# FPGA.net
KiCad netlist of a schematic drawn in Altium Designer
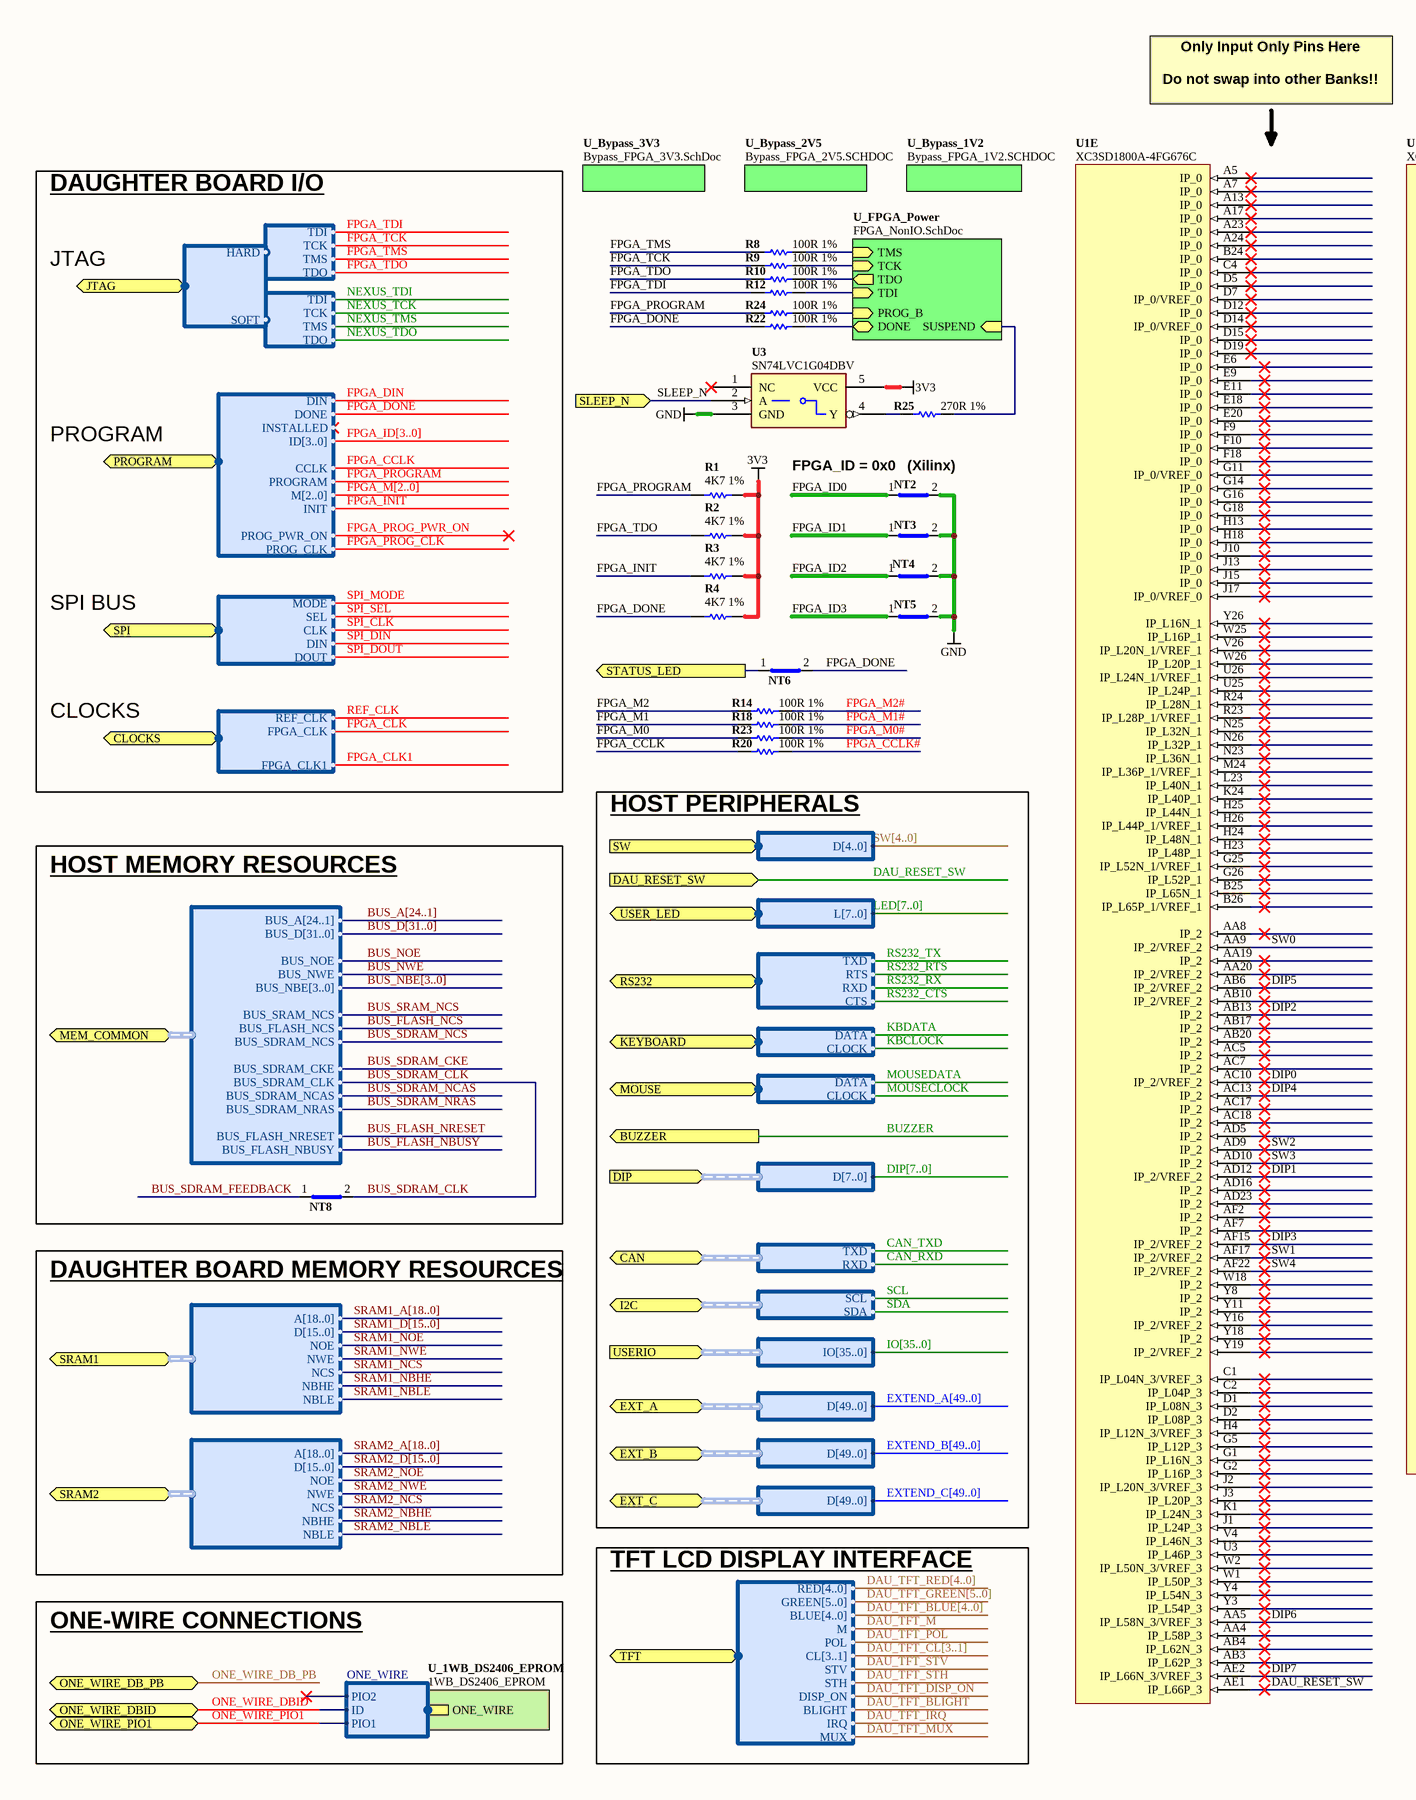
[diagram p0: FPGA.SCHDOC, left]
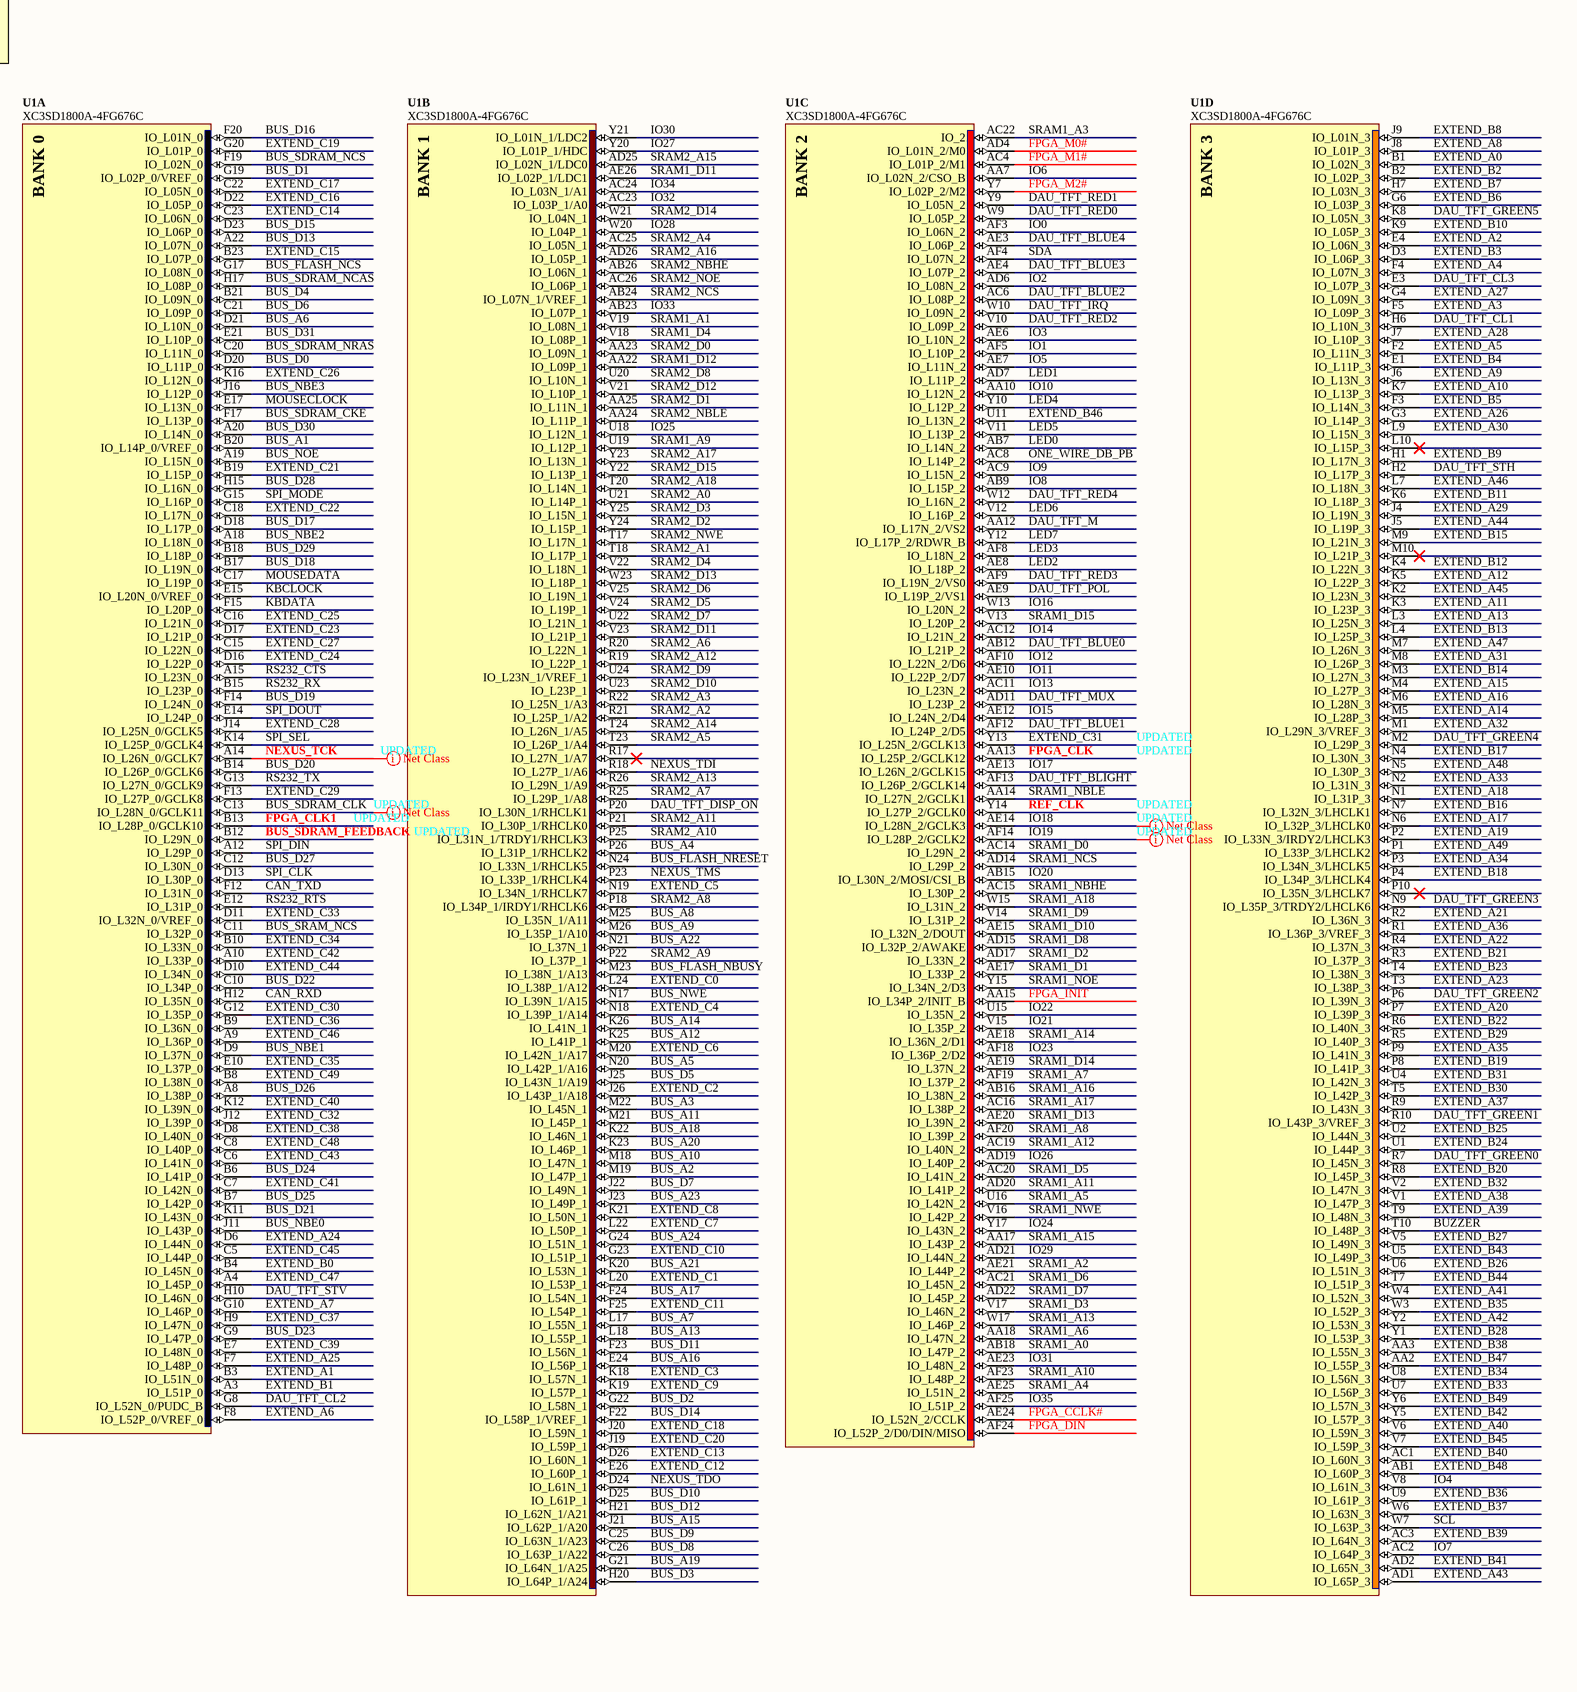
[diagram p1: FPGA.SCHDOC, right]

(export (version "E")
  (design (tool "Eeschema 10.0.6"))
  (components
    (comp (ref "NT2")
      (value "Net Tie SMT2")
      (footprint "NETTIE-SMT2-8X8")
      (description "Net-Tie, Surface Mount, 2 x 0.4mm x 0.2mm SMT Pads - For 0.2mm Track")
      (libsource (lib "AltiumDesignLibrary") (part "NETTIE-SMT2"))
    )
    (comp (ref "NT3")
      (value "Net Tie SMT2")
      (footprint "NETTIE-SMT2-8X8")
      (description "Net-Tie, Surface Mount, 2 x 0.4mm x 0.2mm SMT Pads - For 0.2mm Track")
      (libsource (lib "AltiumDesignLibrary") (part "NETTIE-SMT2"))
    )
    (comp (ref "NT4")
      (value "Net Tie SMT2")
      (footprint "NETTIE-SMT2-8X8")
      (description "Net-Tie, Surface Mount, 2 x 0.4mm x 0.2mm SMT Pads - For 0.2mm Track")
      (libsource (lib "AltiumDesignLibrary") (part "NETTIE-SMT2"))
    )
    (comp (ref "NT5")
      (value "Net Tie SMT2")
      (footprint "NETTIE-SMT2-8X8")
      (description "Net-Tie, Surface Mount, 2 x 0.4mm x 0.2mm SMT Pads - For 0.2mm Track")
      (libsource (lib "AltiumDesignLibrary") (part "NETTIE-SMT2"))
    )
    (comp (ref "NT6")
      (value "Net Tie SMT2")
      (footprint "NETTIE-SMT2-8X8")
      (description "Net-Tie, Surface Mount, 2 x 0.4mm x 0.2mm SMT Pads - For 0.2mm Track")
      (libsource (lib "AltiumDesignLibrary") (part "NETTIE-SMT2"))
    )
    (comp (ref "NT8")
      (value "Net Tie SMT2")
      (footprint "NETTIE-SMT2-8X8")
      (description "Net-Tie, Surface Mount, 2 x 0.4mm x 0.2mm SMT Pads - For 0.2mm Track")
      (libsource (lib "AltiumDesignLibrary") (part "NETTIE-SMT2"))
    )
    (comp (ref "R1")
      (value "4K7 1%")
      (footprint "RESC1005-STAR")
      (description "Resistor, 4K7 1% 0402 (1005)")
      (fields (field (name "TOLERANCE") "1 %"))
      (libsource (lib "AltiumDesignLibrary") (part "RES"))
    )
    (comp (ref "R2")
      (value "4K7 1%")
      (footprint "RESC1005-STAR")
      (description "Resistor, 4K7 1% 0402 (1005)")
      (fields (field (name "TOLERANCE") "1 %"))
      (libsource (lib "AltiumDesignLibrary") (part "RES"))
    )
    (comp (ref "R3")
      (value "4K7 1%")
      (footprint "RESC1005-STAR")
      (description "Resistor, 4K7 1% 0402 (1005)")
      (fields (field (name "TOLERANCE") "1 %"))
      (libsource (lib "AltiumDesignLibrary") (part "RES"))
    )
    (comp (ref "R4")
      (value "4K7 1%")
      (footprint "RESC1005-STAR")
      (description "Resistor, 4K7 1% 0402 (1005)")
      (fields (field (name "TOLERANCE") "1 %"))
      (libsource (lib "AltiumDesignLibrary") (part "RES"))
    )
    (comp (ref "R8")
      (value "100R 1%")
      (footprint "RESC1005-STAR")
      (description "Resistor, 100R 1% 0402 (1005)")
      (fields (field (name "TOLERANCE") "1 %"))
      (libsource (lib "AltiumDesignLibrary") (part "RES"))
    )
    (comp (ref "R9")
      (value "100R 1%")
      (footprint "RESC1005-STAR")
      (description "Resistor, 100R 1% 0402 (1005)")
      (fields (field (name "TOLERANCE") "1 %"))
      (libsource (lib "AltiumDesignLibrary") (part "RES"))
    )
    (comp (ref "R10")
      (value "100R 1%")
      (footprint "RESC1005-STAR")
      (description "Resistor, 100R 1% 0402 (1005)")
      (fields (field (name "TOLERANCE") "1 %"))
      (libsource (lib "AltiumDesignLibrary") (part "RES"))
    )
    (comp (ref "R12")
      (value "100R 1%")
      (footprint "RESC1005-STAR")
      (description "Resistor, 100R 1% 0402 (1005)")
      (fields (field (name "TOLERANCE") "1 %"))
      (libsource (lib "AltiumDesignLibrary") (part "RES"))
    )
    (comp (ref "R14")
      (value "100R 1%")
      (footprint "RESC1005-STAR")
      (description "Resistor, 100R 1% 0402 (1005)")
      (fields (field (name "TOLERANCE") "1 %"))
      (libsource (lib "AltiumDesignLibrary") (part "RES"))
    )
    (comp (ref "R18")
      (value "100R 1%")
      (footprint "RESC1005-STAR")
      (description "Resistor, 100R 1% 0402 (1005)")
      (fields (field (name "TOLERANCE") "1 %"))
      (libsource (lib "AltiumDesignLibrary") (part "RES"))
    )
    (comp (ref "R20")
      (value "100R 1%")
      (footprint "RESC1005-STAR")
      (description "Resistor, 100R 1% 0402 (1005)")
      (fields (field (name "TOLERANCE") "1 %"))
      (libsource (lib "AltiumDesignLibrary") (part "RES"))
    )
    (comp (ref "R22")
      (value "100R 1%")
      (footprint "RESC1005-STAR")
      (description "Resistor, 100R 1% 0402 (1005)")
      (fields (field (name "TOLERANCE") "1 %"))
      (libsource (lib "AltiumDesignLibrary") (part "RES"))
    )
    (comp (ref "R23")
      (value "100R 1%")
      (footprint "RESC1005-STAR")
      (description "Resistor, 100R 1% 0402 (1005)")
      (fields (field (name "TOLERANCE") "1 %"))
      (libsource (lib "AltiumDesignLibrary") (part "RES"))
    )
    (comp (ref "R24")
      (value "100R 1%")
      (footprint "RESC1005-STAR")
      (description "Resistor, 100R 1% 0402 (1005)")
      (fields (field (name "TOLERANCE") "1 %"))
      (libsource (lib "AltiumDesignLibrary") (part "RES"))
    )
    (comp (ref "R25")
      (value "270R 1%")
      (footprint "RESC1005-STAR")
      (description "Resistor, 270R 1% 0402 (1005)")
      (fields (field (name "TOLERANCE") "1 %"))
      (libsource (lib "AltiumDesignLibrary") (part "RES"))
    )
    (comp (ref "U1")
      (value "XC3SD1800A-4FG676C")
      (footprint "BGA100P26X26-676")
      (description "FPGA, Xilinx Spartan 3A-DSP-1800 FG676")
      (libsource (lib "AltiumDesignLibrary") (part "XC3SD1800A-4FG676C"))
    )
    (comp (ref "U3")
      (value "SN74LVC1G04DBV")
      (footprint "SOT95P280-5")
      (description "SN74LVC1G04DBV, Single Inverter Gate, 1.65-V to 5.5-V")
      (libsource (lib "AltiumDesignLibrary") (part "SN74LVC1G04DBV"))
    )
  )
  (nets
    (net (code "17") (name "/BUS_A1") (class "Default")
      (node (ref "U1") (pin "B20") (pinfunction "IO_L14P_0/VREF_0_B20") (pintype "bidirectional"))
    )
    (net (code "18") (name "/BUS_A2") (class "Default")
      (node (ref "U1") (pin "M19") (pinfunction "IO_L47P_1_M19") (pintype "bidirectional"))
    )
    (net (code "19") (name "/BUS_A3") (class "Default")
      (node (ref "U1") (pin "M22") (pinfunction "IO_L45N_1_M22") (pintype "bidirectional"))
    )
    (net (code "20") (name "/BUS_A4") (class "Default")
      (node (ref "U1") (pin "P26") (pinfunction "IO_L31P_1/RHCLK2_P26") (pintype "bidirectional"))
    )
    (net (code "21") (name "/BUS_A5") (class "Default")
      (node (ref "U1") (pin "N20") (pinfunction "IO_L42P_1/A16_N20") (pintype "bidirectional"))
    )
    (net (code "22") (name "/BUS_A6") (class "Default")
      (node (ref "U1") (pin "D21") (pinfunction "IO_L10N_0_D21") (pintype "bidirectional"))
    )
    (net (code "23") (name "/BUS_A7") (class "Default")
      (node (ref "U1") (pin "L17") (pinfunction "IO_L55N_1_L17") (pintype "bidirectional"))
    )
    (net (code "24") (name "/BUS_A8") (class "Default")
      (node (ref "U1") (pin "M25") (pinfunction "IO_L35N_1/A11_M25") (pintype "bidirectional"))
    )
    (net (code "25") (name "/BUS_A9") (class "Default")
      (node (ref "U1") (pin "M26") (pinfunction "IO_L35P_1/A10_M26") (pintype "bidirectional"))
    )
    (net (code "26") (name "/BUS_A10") (class "Default")
      (node (ref "U1") (pin "M18") (pinfunction "IO_L47N_1_M18") (pintype "bidirectional"))
    )
    (net (code "27") (name "/BUS_A11") (class "Default")
      (node (ref "U1") (pin "M21") (pinfunction "IO_L45P_1_M21") (pintype "bidirectional"))
    )
    (net (code "28") (name "/BUS_A12") (class "Default")
      (node (ref "U1") (pin "K25") (pinfunction "IO_L41P_1_K25") (pintype "bidirectional"))
    )
    (net (code "29") (name "/BUS_A13") (class "Default")
      (node (ref "U1") (pin "L18") (pinfunction "IO_L55P_1_L18") (pintype "bidirectional"))
    )
    (net (code "30") (name "/BUS_A14") (class "Default")
      (node (ref "U1") (pin "K26") (pinfunction "IO_L41N_1_K26") (pintype "bidirectional"))
    )
    (net (code "31") (name "/BUS_A15") (class "Default")
      (node (ref "U1") (pin "J21") (pinfunction "IO_L62P_1/A20_J21") (pintype "bidirectional"))
    )
    (net (code "32") (name "/BUS_A16") (class "Default")
      (node (ref "U1") (pin "E24") (pinfunction "IO_L56P_1_E24") (pintype "bidirectional"))
    )
    (net (code "33") (name "/BUS_A17") (class "Default")
      (node (ref "U1") (pin "F24") (pinfunction "IO_L54N_1_F24") (pintype "bidirectional"))
    )
    (net (code "34") (name "/BUS_A18") (class "Default")
      (node (ref "U1") (pin "K22") (pinfunction "IO_L46N_1_K22") (pintype "bidirectional"))
    )
    (net (code "35") (name "/BUS_A19") (class "Default")
      (node (ref "U1") (pin "G21") (pinfunction "IO_L64N_1/A25_G21") (pintype "bidirectional"))
    )
    (net (code "36") (name "/BUS_A20") (class "Default")
      (node (ref "U1") (pin "K23") (pinfunction "IO_L46P_1_K23") (pintype "bidirectional"))
    )
    (net (code "37") (name "/BUS_A21") (class "Default")
      (node (ref "U1") (pin "K20") (pinfunction "IO_L53N_1_K20") (pintype "bidirectional"))
    )
    (net (code "38") (name "/BUS_A22") (class "Default")
      (node (ref "U1") (pin "N21") (pinfunction "IO_L37N_1_N21") (pintype "bidirectional"))
    )
    (net (code "39") (name "/BUS_A23") (class "Default")
      (node (ref "U1") (pin "J23") (pinfunction "IO_L49P_1_J23") (pintype "bidirectional"))
    )
    (net (code "40") (name "/BUS_A24") (class "Default")
      (node (ref "U1") (pin "G24") (pinfunction "IO_L51N_1_G24") (pintype "bidirectional"))
    )
    (net (code "41") (name "/BUS_D0") (class "Default")
      (node (ref "U1") (pin "D20") (pinfunction "IO_L11P_0_D20") (pintype "bidirectional"))
    )
    (net (code "42") (name "/BUS_D1") (class "Default")
      (node (ref "U1") (pin "G19") (pinfunction "IO_L02P_0/VREF_0_G19") (pintype "bidirectional"))
    )
    (net (code "43") (name "/BUS_D2") (class "Default")
      (node (ref "U1") (pin "G22") (pinfunction "IO_L58N_1_G22") (pintype "bidirectional"))
    )
    (net (code "44") (name "/BUS_D3") (class "Default")
      (node (ref "U1") (pin "H20") (pinfunction "IO_L64P_1/A24_H20") (pintype "bidirectional"))
    )
    (net (code "45") (name "/BUS_D4") (class "Default")
      (node (ref "U1") (pin "B21") (pinfunction "IO_L09N_0_B21") (pintype "bidirectional"))
    )
    (net (code "46") (name "/BUS_D5") (class "Default")
      (node (ref "U1") (pin "J25") (pinfunction "IO_L43N_1/A19_J25") (pintype "bidirectional"))
    )
    (net (code "47") (name "/BUS_D6") (class "Default")
      (node (ref "U1") (pin "C21") (pinfunction "IO_L09P_0_C21") (pintype "bidirectional"))
    )
    (net (code "48") (name "/BUS_D7") (class "Default")
      (node (ref "U1") (pin "J22") (pinfunction "IO_L49N_1_J22") (pintype "bidirectional"))
    )
    (net (code "49") (name "/BUS_D8") (class "Default")
      (node (ref "U1") (pin "C26") (pinfunction "IO_L63P_1/A22_C26") (pintype "bidirectional"))
    )
    (net (code "50") (name "/BUS_D9") (class "Default")
      (node (ref "U1") (pin "C25") (pinfunction "IO_L63N_1/A23_C25") (pintype "bidirectional"))
    )
    (net (code "51") (name "/BUS_D10") (class "Default")
      (node (ref "U1") (pin "D25") (pinfunction "IO_L61P_1_D25") (pintype "bidirectional"))
    )
    (net (code "52") (name "/BUS_D11") (class "Default")
      (node (ref "U1") (pin "F23") (pinfunction "IO_L56N_1_F23") (pintype "bidirectional"))
    )
    (net (code "53") (name "/BUS_D12") (class "Default")
      (node (ref "U1") (pin "H21") (pinfunction "IO_L62N_1/A21_H21") (pintype "bidirectional"))
    )
    (net (code "54") (name "/BUS_D13") (class "Default")
      (node (ref "U1") (pin "A22") (pinfunction "IO_L07N_0_A22") (pintype "bidirectional"))
    )
    (net (code "55") (name "/BUS_D14") (class "Default")
      (node (ref "U1") (pin "F22") (pinfunction "IO_L58P_1/VREF_1_F22") (pintype "bidirectional"))
    )
    (net (code "56") (name "/BUS_D15") (class "Default")
      (node (ref "U1") (pin "D23") (pinfunction "IO_L06P_0_D23") (pintype "bidirectional"))
    )
    (net (code "57") (name "/BUS_D16") (class "Default")
      (node (ref "U1") (pin "F20") (pinfunction "IO_L01N_0_F20") (pintype "bidirectional"))
    )
    (net (code "58") (name "/BUS_D17") (class "Default")
      (node (ref "U1") (pin "D18") (pinfunction "IO_L17P_0_D18") (pintype "bidirectional"))
    )
    (net (code "59") (name "/BUS_D18") (class "Default")
      (node (ref "U1") (pin "B17") (pinfunction "IO_L19N_0_B17") (pintype "bidirectional"))
    )
    (net (code "60") (name "/BUS_D19") (class "Default")
      (node (ref "U1") (pin "F14") (pinfunction "IO_L24N_0_F14") (pintype "bidirectional"))
    )
    (net (code "61") (name "/BUS_D20") (class "Default")
      (node (ref "U1") (pin "B14") (pinfunction "IO_L26P_0/GCLK6_B14") (pintype "bidirectional"))
    )
    (net (code "62") (name "/BUS_D21") (class "Default")
      (node (ref "U1") (pin "K11") (pinfunction "IO_L43N_0_K11") (pintype "bidirectional"))
    )
    (net (code "63") (name "/BUS_D22") (class "Default")
      (node (ref "U1") (pin "C10") (pinfunction "IO_L34P_0_C10") (pintype "bidirectional"))
    )
    (net (code "64") (name "/BUS_D23") (class "Default")
      (node (ref "U1") (pin "G9") (pinfunction "IO_L47P_0_G9") (pintype "bidirectional"))
    )
    (net (code "65") (name "/BUS_D24") (class "Default")
      (node (ref "U1") (pin "B6") (pinfunction "IO_L41P_0_B6") (pintype "bidirectional"))
    )
    (net (code "66") (name "/BUS_D25") (class "Default")
      (node (ref "U1") (pin "B7") (pinfunction "IO_L42P_0_B7") (pintype "bidirectional"))
    )
    (net (code "67") (name "/BUS_D26") (class "Default")
      (node (ref "U1") (pin "A8") (pinfunction "IO_L38P_0_A8") (pintype "bidirectional"))
    )
    (net (code "68") (name "/BUS_D27") (class "Default")
      (node (ref "U1") (pin "C12") (pinfunction "IO_L30N_0_C12") (pintype "bidirectional"))
    )
    (net (code "69") (name "/BUS_D28") (class "Default")
      (node (ref "U1") (pin "H15") (pinfunction "IO_L16N_0_H15") (pintype "bidirectional"))
    )
    (net (code "70") (name "/BUS_D29") (class "Default")
      (node (ref "U1") (pin "B18") (pinfunction "IO_L18P_0_B18") (pintype "bidirectional"))
    )
    (net (code "71") (name "/BUS_D30") (class "Default")
      (node (ref "U1") (pin "A20") (pinfunction "IO_L14N_0_A20") (pintype "bidirectional"))
    )
    (net (code "72") (name "/BUS_D31") (class "Default")
      (node (ref "U1") (pin "E21") (pinfunction "IO_L10P_0_E21") (pintype "bidirectional"))
    )
    (net (code "74") (name "/BUS_FLASH_NBUSY") (class "Default")
      (node (ref "U1") (pin "M23") (pinfunction "IO_L38N_1/A13_M23") (pintype "bidirectional"))
    )
    (net (code "75") (name "/BUS_FLASH_NCS") (class "Default")
      (node (ref "U1") (pin "G17") (pinfunction "IO_L08N_0_G17") (pintype "bidirectional"))
    )
    (net (code "76") (name "/BUS_FLASH_NRESET") (class "Default")
      (node (ref "U1") (pin "N24") (pinfunction "IO_L33N_1/RHCLK5_N24") (pintype "bidirectional"))
    )
    (net (code "77") (name "/BUS_NBE0") (class "Default")
      (node (ref "U1") (pin "J11") (pinfunction "IO_L43P_0_J11") (pintype "bidirectional"))
    )
    (net (code "78") (name "/BUS_NBE1") (class "Default")
      (node (ref "U1") (pin "D9") (pinfunction "IO_L37N_0_D9") (pintype "bidirectional"))
    )
    (net (code "79") (name "/BUS_NBE2") (class "Default")
      (node (ref "U1") (pin "A18") (pinfunction "IO_L18N_0_A18") (pintype "bidirectional"))
    )
    (net (code "80") (name "/BUS_NBE3") (class "Default")
      (node (ref "U1") (pin "J16") (pinfunction "IO_L12P_0_J16") (pintype "bidirectional"))
    )
    (net (code "82") (name "/BUS_NOE") (class "Default")
      (node (ref "U1") (pin "A19") (pinfunction "IO_L15N_0_A19") (pintype "bidirectional"))
    )
    (net (code "83") (name "/BUS_NWE") (class "Default")
      (node (ref "U1") (pin "N17") (pinfunction "IO_L39N_1/A15_N17") (pintype "bidirectional"))
    )
    (net (code "84") (name "/BUS_SDRAM_CKE") (class "Default")
      (node (ref "U1") (pin "F17") (pinfunction "IO_L13P_0_F17") (pintype "bidirectional"))
    )
    (net (code "85") (name "/BUS_SDRAM_CLK") (class "Default")
      (node (ref "NT8") (pin "2") (pinfunction "Net2_2") (pintype "passive"))
      (node (ref "U1") (pin "C13") (pinfunction "IO_L28N_0/GCLK11_C13") (pintype "bidirectional"))
    )
    (net (code "86") (name "/BUS_SDRAM_FEEDBACK") (class "Default")
      (node (ref "NT8") (pin "1") (pinfunction "Net1_1") (pintype "passive"))
      (node (ref "U1") (pin "B12") (pinfunction "IO_L29N_0_B12") (pintype "bidirectional"))
    )
    (net (code "87") (name "/BUS_SDRAM_NCAS") (class "Default")
      (node (ref "U1") (pin "H17") (pinfunction "IO_L08P_0_H17") (pintype "bidirectional"))
    )
    (net (code "88") (name "/BUS_SDRAM_NCS") (class "Default")
      (node (ref "U1") (pin "F19") (pinfunction "IO_L02N_0_F19") (pintype "bidirectional"))
    )
    (net (code "89") (name "/BUS_SDRAM_NRAS") (class "Default")
      (node (ref "U1") (pin "C20") (pinfunction "IO_L11N_0_C20") (pintype "bidirectional"))
    )
    (net (code "90") (name "/BUS_SRAM_NCS") (class "Default")
      (node (ref "U1") (pin "C11") (pinfunction "IO_L32P_0_C11") (pintype "bidirectional"))
    )
    (net (code "91") (name "/BUZZER") (class "Default")
      (node (ref "U1") (pin "T10") (pinfunction "IO_L48P_3_T10") (pintype "bidirectional"))
    )
    (net (code "92") (name "/CAN_RXD") (class "Default")
      (node (ref "U1") (pin "H12") (pinfunction "IO_L35N_0_H12") (pintype "bidirectional"))
    )
    (net (code "93") (name "/CAN_TXD") (class "Default")
      (node (ref "U1") (pin "F12") (pinfunction "IO_L31N_0_F12") (pintype "bidirectional"))
    )
    (net (code "94") (name "/DAU_RESET_SW") (class "Default")
      (node (ref "U1") (pin "AE1") (pinfunction "IP_L66P_3_AE1") (pintype "input"))
    )
    (net (code "95") (name "/DAU_TFT_BLIGHT") (class "Default")
      (node (ref "U1") (pin "AF13") (pinfunction "IO_L26P_2/GCLK14_AF13") (pintype "bidirectional"))
    )
    (net (code "96") (name "/DAU_TFT_BLUE0") (class "Default")
      (node (ref "U1") (pin "AB12") (pinfunction "IO_L21P_2_AB12") (pintype "bidirectional"))
    )
    (net (code "97") (name "/DAU_TFT_BLUE1") (class "Default")
      (node (ref "U1") (pin "AF12") (pinfunction "IO_L24P_2/D5_AF12") (pintype "bidirectional"))
    )
    (net (code "98") (name "/DAU_TFT_BLUE2") (class "Default")
      (node (ref "U1") (pin "AC6") (pinfunction "IO_L08P_2_AC6") (pintype "bidirectional"))
    )
    (net (code "99") (name "/DAU_TFT_BLUE3") (class "Default")
      (node (ref "U1") (pin "AE4") (pinfunction "IO_L07P_2_AE4") (pintype "bidirectional"))
    )
    (net (code "100") (name "/DAU_TFT_BLUE4") (class "Default")
      (node (ref "U1") (pin "AE3") (pinfunction "IO_L06P_2_AE3") (pintype "bidirectional"))
    )
    (net (code "102") (name "/DAU_TFT_CL1") (class "Default")
      (node (ref "U1") (pin "H6") (pinfunction "IO_L10N_3_H6") (pintype "bidirectional"))
    )
    (net (code "103") (name "/DAU_TFT_CL2") (class "Default")
      (node (ref "U1") (pin "G8") (pinfunction "IO_L52N_0/PUDC_B_G8") (pintype "bidirectional"))
    )
    (net (code "104") (name "/DAU_TFT_CL3") (class "Default")
      (node (ref "U1") (pin "E3") (pinfunction "IO_L07P_3_E3") (pintype "bidirectional"))
    )
    (net (code "105") (name "/DAU_TFT_DISP_ON") (class "Default")
      (node (ref "U1") (pin "P20") (pinfunction "IO_L30N_1/RHCLK1_P20") (pintype "bidirectional"))
    )
    (net (code "106") (name "/DAU_TFT_GREEN0") (class "Default")
      (node (ref "U1") (pin "R7") (pinfunction "IO_L45N_3_R7") (pintype "bidirectional"))
    )
    (net (code "107") (name "/DAU_TFT_GREEN1") (class "Default")
      (node (ref "U1") (pin "R10") (pinfunction "IO_L43P_3/VREF_3_R10") (pintype "bidirectional"))
    )
    (net (code "108") (name "/DAU_TFT_GREEN2") (class "Default")
      (node (ref "U1") (pin "P6") (pinfunction "IO_L39N_3_P6") (pintype "bidirectional"))
    )
    (net (code "109") (name "/DAU_TFT_GREEN3") (class "Default")
      (node (ref "U1") (pin "N9") (pinfunction "IO_L35P_3/TRDY2/LHCLK6_N9") (pintype "bidirectional"))
    )
    (net (code "110") (name "/DAU_TFT_GREEN4") (class "Default")
      (node (ref "U1") (pin "M2") (pinfunction "IO_L29P_3_M2") (pintype "bidirectional"))
    )
    (net (code "111") (name "/DAU_TFT_GREEN5") (class "Default")
      (node (ref "U1") (pin "K8") (pinfunction "IO_L05N_3_K8") (pintype "bidirectional"))
    )
    (net (code "113") (name "/DAU_TFT_IRQ") (class "Default")
      (node (ref "U1") (pin "W10") (pinfunction "IO_L09N_2_W10") (pintype "bidirectional"))
    )
    (net (code "114") (name "/DAU_TFT_M") (class "Default")
      (node (ref "U1") (pin "AA12") (pinfunction "IO_L17N_2/VS2_AA12") (pintype "bidirectional"))
    )
    (net (code "115") (name "/DAU_TFT_MUX") (class "Default")
      (node (ref "U1") (pin "AD11") (pinfunction "IO_L23P_2_AD11") (pintype "bidirectional"))
    )
    (net (code "116") (name "/DAU_TFT_POL") (class "Default")
      (node (ref "U1") (pin "AE9") (pinfunction "IO_L19P_2/VS1_AE9") (pintype "bidirectional"))
    )
    (net (code "117") (name "/DAU_TFT_RED0") (class "Default")
      (node (ref "U1") (pin "W9") (pinfunction "IO_L05P_2_W9") (pintype "bidirectional"))
    )
    (net (code "118") (name "/DAU_TFT_RED1") (class "Default")
      (node (ref "U1") (pin "Y9") (pinfunction "IO_L05N_2_Y9") (pintype "bidirectional"))
    )
    (net (code "119") (name "/DAU_TFT_RED2") (class "Default")
      (node (ref "U1") (pin "V10") (pinfunction "IO_L09P_2_V10") (pintype "bidirectional"))
    )
    (net (code "120") (name "/DAU_TFT_RED3") (class "Default")
      (node (ref "U1") (pin "AF9") (pinfunction "IO_L19N_2/VS0_AF9") (pintype "bidirectional"))
    )
    (net (code "121") (name "/DAU_TFT_RED4") (class "Default")
      (node (ref "U1") (pin "W12") (pinfunction "IO_L16N_2_W12") (pintype "bidirectional"))
    )
    (net (code "123") (name "/DAU_TFT_STH") (class "Default")
      (node (ref "U1") (pin "H2") (pinfunction "IO_L17P_3_H2") (pintype "bidirectional"))
    )
    (net (code "124") (name "/DAU_TFT_STV") (class "Default")
      (node (ref "U1") (pin "H10") (pinfunction "IO_L46N_0_H10") (pintype "bidirectional"))
    )
    (net (code "125") (name "/DIP0") (class "Default")
      (node (ref "U1") (pin "AC10") (pinfunction "IP_2/VREF_2_AC10") (pintype "input"))
    )
    (net (code "126") (name "/DIP1") (class "Default")
      (node (ref "U1") (pin "AD12") (pinfunction "IP_2/VREF_2_AD12") (pintype "input"))
    )
    (net (code "127") (name "/DIP2") (class "Default")
      (node (ref "U1") (pin "AB13") (pinfunction "IP_2_AB13") (pintype "input"))
    )
    (net (code "128") (name "/DIP3") (class "Default")
      (node (ref "U1") (pin "AF15") (pinfunction "IP_2/VREF_2_AF15") (pintype "input"))
    )
    (net (code "129") (name "/DIP4") (class "Default")
      (node (ref "U1") (pin "AC13") (pinfunction "IP_2_AC13") (pintype "input"))
    )
    (net (code "130") (name "/DIP5") (class "Default")
      (node (ref "U1") (pin "AB6") (pinfunction "IP_2/VREF_2_AB6") (pintype "input"))
    )
    (net (code "131") (name "/DIP6") (class "Default")
      (node (ref "U1") (pin "AA5") (pinfunction "IP_L58N_3/VREF_3_AA5") (pintype "input"))
    )
    (net (code "132") (name "/DIP7") (class "Default")
      (node (ref "U1") (pin "AE2") (pinfunction "IP_L66N_3/VREF_3_AE2") (pintype "input"))
    )
    (net (code "134") (name "/DONE") (class "Default")
      (node (ref "R22") (pin "2") (pinfunction "2_2") (pintype "passive"))
    )
    (net (code "135") (name "/EXTEND_A0") (class "Default")
      (node (ref "U1") (pin "B1") (pinfunction "IO_L02N_3_B1") (pintype "bidirectional"))
    )
    (net (code "136") (name "/EXTEND_A1") (class "Default")
      (node (ref "U1") (pin "B3") (pinfunction "IO_L51N_0_B3") (pintype "bidirectional"))
    )
    (net (code "137") (name "/EXTEND_A2") (class "Default")
      (node (ref "U1") (pin "E4") (pinfunction "IO_L06N_3_E4") (pintype "bidirectional"))
    )
    (net (code "138") (name "/EXTEND_A3") (class "Default")
      (node (ref "U1") (pin "F5") (pinfunction "IO_L09P_3_F5") (pintype "bidirectional"))
    )
    (net (code "139") (name "/EXTEND_A4") (class "Default")
      (node (ref "U1") (pin "F4") (pinfunction "IO_L07N_3_F4") (pintype "bidirectional"))
    )
    (net (code "140") (name "/EXTEND_A5") (class "Default")
      (node (ref "U1") (pin "F2") (pinfunction "IO_L11N_3_F2") (pintype "bidirectional"))
    )
    (net (code "141") (name "/EXTEND_A6") (class "Default")
      (node (ref "U1") (pin "F8") (pinfunction "IO_L52P_0/VREF_0_F8") (pintype "bidirectional"))
    )
    (net (code "142") (name "/EXTEND_A7") (class "Default")
      (node (ref "U1") (pin "G10") (pinfunction "IO_L46P_0_G10") (pintype "bidirectional"))
    )
    (net (code "143") (name "/EXTEND_A8") (class "Default")
      (node (ref "U1") (pin "J8") (pinfunction "IO_L01P_3_J8") (pintype "bidirectional"))
    )
    (net (code "144") (name "/EXTEND_A9") (class "Default")
      (node (ref "U1") (pin "J6") (pinfunction "IO_L13N_3_J6") (pintype "bidirectional"))
    )
    (net (code "145") (name "/EXTEND_A10") (class "Default")
      (node (ref "U1") (pin "K7") (pinfunction "IO_L13P_3_K7") (pintype "bidirectional"))
    )
    (net (code "146") (name "/EXTEND_A11") (class "Default")
      (node (ref "U1") (pin "K3") (pinfunction "IO_L23P_3_K3") (pintype "bidirectional"))
    )
    (net (code "147") (name "/EXTEND_A12") (class "Default")
      (node (ref "U1") (pin "K5") (pinfunction "IO_L22P_3_K5") (pintype "bidirectional"))
    )
    (net (code "148") (name "/EXTEND_A13") (class "Default")
      (node (ref "U1") (pin "L3") (pinfunction "IO_L25N_3_L3") (pintype "bidirectional"))
    )
    (net (code "149") (name "/EXTEND_A14") (class "Default")
      (node (ref "U1") (pin "M5") (pinfunction "IO_L28P_3_M5") (pintype "bidirectional"))
    )
    (net (code "150") (name "/EXTEND_A15") (class "Default")
      (node (ref "U1") (pin "M4") (pinfunction "IO_L27P_3_M4") (pintype "bidirectional"))
    )
    (net (code "151") (name "/EXTEND_A16") (class "Default")
      (node (ref "U1") (pin "M6") (pinfunction "IO_L28N_3_M6") (pintype "bidirectional"))
    )
    (net (code "152") (name "/EXTEND_A17") (class "Default")
      (node (ref "U1") (pin "N6") (pinfunction "IO_L32P_3/LHCLK0_N6") (pintype "bidirectional"))
    )
    (net (code "153") (name "/EXTEND_A18") (class "Default")
      (node (ref "U1") (pin "N1") (pinfunction "IO_L31P_3_N1") (pintype "bidirectional"))
    )
    (net (code "154") (name "/EXTEND_A19") (class "Default")
      (node (ref "U1") (pin "P2") (pinfunction "IO_L33N_3/IRDY2/LHCLK3_P2") (pintype "bidirectional"))
    )
    (net (code "155") (name "/EXTEND_A20") (class "Default")
      (node (ref "U1") (pin "P7") (pinfunction "IO_L39P_3_P7") (pintype "bidirectional"))
    )
    (net (code "156") (name "/EXTEND_A21") (class "Default")
      (node (ref "U1") (pin "R2") (pinfunction "IO_L36N_3_R2") (pintype "bidirectional"))
    )
    (net (code "157") (name "/EXTEND_A22") (class "Default")
      (node (ref "U1") (pin "R4") (pinfunction "IO_L37N_3_R4") (pintype "bidirectional"))
    )
    (net (code "158") (name "/EXTEND_A23") (class "Default")
      (node (ref "U1") (pin "T3") (pinfunction "IO_L38P_3_T3") (pintype "bidirectional"))
    )
    (net (code "159") (name "/EXTEND_A24") (class "Default")
      (node (ref "U1") (pin "D6") (pinfunction "IO_L44N_0_D6") (pintype "bidirectional"))
    )
    (net (code "160") (name "/EXTEND_A25") (class "Default")
      (node (ref "U1") (pin "F7") (pinfunction "IO_L48P_0_F7") (pintype "bidirectional"))
    )
    (net (code "161") (name "/EXTEND_A26") (class "Default")
      (node (ref "U1") (pin "G3") (pinfunction "IO_L14P_3_G3") (pintype "bidirectional"))
    )
    (net (code "162") (name "/EXTEND_A27") (class "Default")
      (node (ref "U1") (pin "G4") (pinfunction "IO_L09N_3_G4") (pintype "bidirectional"))
    )
    (net (code "163") (name "/EXTEND_A28") (class "Default")
      (node (ref "U1") (pin "J7") (pinfunction "IO_L10P_3_J7") (pintype "bidirectional"))
    )
    (net (code "164") (name "/EXTEND_A29") (class "Default")
      (node (ref "U1") (pin "J4") (pinfunction "IO_L19N_3_J4") (pintype "bidirectional"))
    )
    (net (code "165") (name "/EXTEND_A30") (class "Default")
      (node (ref "U1") (pin "L9") (pinfunction "IO_L15N_3_L9") (pintype "bidirectional"))
    )
    (net (code "166") (name "/EXTEND_A31") (class "Default")
      (node (ref "U1") (pin "M8") (pinfunction "IO_L26P_3_M8") (pintype "bidirectional"))
    )
    (net (code "167") (name "/EXTEND_A32") (class "Default")
      (node (ref "U1") (pin "M1") (pinfunction "IO_L29N_3/VREF_3_M1") (pintype "bidirectional"))
    )
    (net (code "168") (name "/EXTEND_A33") (class "Default")
      (node (ref "U1") (pin "N2") (pinfunction "IO_L31N_3_N2") (pintype "bidirectional"))
    )
    (net (code "169") (name "/EXTEND_A34") (class "Default")
      (node (ref "U1") (pin "P3") (pinfunction "IO_L34N_3/LHCLK5_P3") (pintype "bidirectional"))
    )
    (net (code "170") (name "/EXTEND_A35") (class "Default")
      (node (ref "U1") (pin "P9") (pinfunction "IO_L41N_3_P9") (pintype "bidirectional"))
    )
    (net (code "171") (name "/EXTEND_A36") (class "Default")
      (node (ref "U1") (pin "R1") (pinfunction "IO_L36P_3/VREF_3_R1") (pintype "bidirectional"))
    )
    (net (code "172") (name "/EXTEND_A37") (class "Default")
      (node (ref "U1") (pin "R9") (pinfunction "IO_L43N_3_R9") (pintype "bidirectional"))
    )
    (net (code "173") (name "/EXTEND_A38") (class "Default")
      (node (ref "U1") (pin "V1") (pinfunction "IO_L47P_3_V1") (pintype "bidirectional"))
    )
    (net (code "174") (name "/EXTEND_A39") (class "Default")
      (node (ref "U1") (pin "T9") (pinfunction "IO_L48N_3_T9") (pintype "bidirectional"))
    )
    (net (code "175") (name "/EXTEND_A40") (class "Default")
      (node (ref "U1") (pin "V6") (pinfunction "IO_L59N_3_V6") (pintype "bidirectional"))
    )
    (net (code "176") (name "/EXTEND_A41") (class "Default")
      (node (ref "U1") (pin "W4") (pinfunction "IO_L52N_3_W4") (pintype "bidirectional"))
    )
    (net (code "177") (name "/EXTEND_A42") (class "Default")
      (node (ref "U1") (pin "Y2") (pinfunction "IO_L53N_3_Y2") (pintype "bidirectional"))
    )
    (net (code "178") (name "/EXTEND_A43") (class "Default")
      (node (ref "U1") (pin "AD1") (pinfunction "IO_L65P_3_AD1") (pintype "bidirectional"))
    )
    (net (code "179") (name "/EXTEND_A44") (class "Default")
      (node (ref "U1") (pin "J5") (pinfunction "IO_L19P_3_J5") (pintype "bidirectional"))
    )
    (net (code "180") (name "/EXTEND_A45") (class "Default")
      (node (ref "U1") (pin "K2") (pinfunction "IO_L23N_3_K2") (pintype "bidirectional"))
    )
    (net (code "181") (name "/EXTEND_A46") (class "Default")
      (node (ref "U1") (pin "L7") (pinfunction "IO_L18N_3_L7") (pintype "bidirectional"))
    )
    (net (code "182") (name "/EXTEND_A47") (class "Default")
      (node (ref "U1") (pin "M7") (pinfunction "IO_L26N_3_M7") (pintype "bidirectional"))
    )
    (net (code "183") (name "/EXTEND_A48") (class "Default")
      (node (ref "U1") (pin "N5") (pinfunction "IO_L30P_3_N5") (pintype "bidirectional"))
    )
    (net (code "184") (name "/EXTEND_A49") (class "Default")
      (node (ref "U1") (pin "P1") (pinfunction "IO_L33P_3/LHCLK2_P1") (pintype "bidirectional"))
    )
    (net (code "186") (name "/EXTEND_B0") (class "Default")
      (node (ref "U1") (pin "B4") (pinfunction "IO_L45N_0_B4") (pintype "bidirectional"))
    )
    (net (code "187") (name "/EXTEND_B1") (class "Default")
      (node (ref "U1") (pin "A3") (pinfunction "IO_L51P_0_A3") (pintype "bidirectional"))
    )
    (net (code "188") (name "/EXTEND_B2") (class "Default")
      (node (ref "U1") (pin "B2") (pinfunction "IO_L02P_3_B2") (pintype "bidirectional"))
    )
    (net (code "189") (name "/EXTEND_B3") (class "Default")
      (node (ref "U1") (pin "D3") (pinfunction "IO_L06P_3_D3") (pintype "bidirectional"))
    )
    (net (code "190") (name "/EXTEND_B4") (class "Default")
      (node (ref "U1") (pin "E1") (pinfunction "IO_L11P_3_E1") (pintype "bidirectional"))
    )
    (net (code "191") (name "/EXTEND_B5") (class "Default")
      (node (ref "U1") (pin "F3") (pinfunction "IO_L14N_3_F3") (pintype "bidirectional"))
    )
    (net (code "192") (name "/EXTEND_B6") (class "Default")
      (node (ref "U1") (pin "G6") (pinfunction "IO_L03P_3_G6") (pintype "bidirectional"))
    )
    (net (code "193") (name "/EXTEND_B7") (class "Default")
      (node (ref "U1") (pin "H7") (pinfunction "IO_L03N_3_H7") (pintype "bidirectional"))
    )
    (net (code "194") (name "/EXTEND_B8") (class "Default")
      (node (ref "U1") (pin "J9") (pinfunction "IO_L01N_3_J9") (pintype "bidirectional"))
    )
    (net (code "195") (name "/EXTEND_B9") (class "Default")
      (node (ref "U1") (pin "H1") (pinfunction "IO_L17N_3_H1") (pintype "bidirectional"))
    )
    (net (code "196") (name "/EXTEND_B10") (class "Default")
      (node (ref "U1") (pin "K9") (pinfunction "IO_L05P_3_K9") (pintype "bidirectional"))
    )
    (net (code "197") (name "/EXTEND_B11") (class "Default")
      (node (ref "U1") (pin "K6") (pinfunction "IO_L18P_3_K6") (pintype "bidirectional"))
    )
    (net (code "198") (name "/EXTEND_B12") (class "Default")
      (node (ref "U1") (pin "K4") (pinfunction "IO_L22N_3_K4") (pintype "bidirectional"))
    )
    (net (code "199") (name "/EXTEND_B13") (class "Default")
      (node (ref "U1") (pin "L4") (pinfunction "IO_L25P_3_L4") (pintype "bidirectional"))
    )
    (net (code "200") (name "/EXTEND_B14") (class "Default")
      (node (ref "U1") (pin "M3") (pinfunction "IO_L27N_3_M3") (pintype "bidirectional"))
    )
    (net (code "201") (name "/EXTEND_B15") (class "Default")
      (node (ref "U1") (pin "M9") (pinfunction "IO_L21N_3_M9") (pintype "bidirectional"))
    )
    (net (code "202") (name "/EXTEND_B16") (class "Default")
      (node (ref "U1") (pin "N7") (pinfunction "IO_L32N_3/LHCLK1_N7") (pintype "bidirectional"))
    )
    (net (code "203") (name "/EXTEND_B17") (class "Default")
      (node (ref "U1") (pin "N4") (pinfunction "IO_L30N_3_N4") (pintype "bidirectional"))
    )
    (net (code "204") (name "/EXTEND_B18") (class "Default")
      (node (ref "U1") (pin "P4") (pinfunction "IO_L34P_3/LHCLK4_P4") (pintype "bidirectional"))
    )
    (net (code "205") (name "/EXTEND_B19") (class "Default")
      (node (ref "U1") (pin "P8") (pinfunction "IO_L41P_3_P8") (pintype "bidirectional"))
    )
    (net (code "206") (name "/EXTEND_B20") (class "Default")
      (node (ref "U1") (pin "R8") (pinfunction "IO_L45P_3_R8") (pintype "bidirectional"))
    )
    (net (code "207") (name "/EXTEND_B21") (class "Default")
      (node (ref "U1") (pin "R3") (pinfunction "IO_L37P_3_R3") (pintype "bidirectional"))
    )
    (net (code "208") (name "/EXTEND_B22") (class "Default")
      (node (ref "U1") (pin "R6") (pinfunction "IO_L40N_3_R6") (pintype "bidirectional"))
    )
    (net (code "209") (name "/EXTEND_B23") (class "Default")
      (node (ref "U1") (pin "T4") (pinfunction "IO_L38N_3_T4") (pintype "bidirectional"))
    )
    (net (code "210") (name "/EXTEND_B24") (class "Default")
      (node (ref "U1") (pin "U1") (pinfunction "IO_L44P_3_U1") (pintype "bidirectional"))
    )
    (net (code "211") (name "/EXTEND_B25") (class "Default")
      (node (ref "U1") (pin "U2") (pinfunction "IO_L44N_3_U2") (pintype "bidirectional"))
    )
    (net (code "212") (name "/EXTEND_B26") (class "Default")
      (node (ref "U1") (pin "U6") (pinfunction "IO_L51N_3_U6") (pintype "bidirectional"))
    )
    (net (code "213") (name "/EXTEND_B27") (class "Default")
      (node (ref "U1") (pin "V5") (pinfunction "IO_L49N_3_V5") (pintype "bidirectional"))
    )
    (net (code "214") (name "/EXTEND_B28") (class "Default")
      (node (ref "U1") (pin "Y1") (pinfunction "IO_L53P_3_Y1") (pintype "bidirectional"))
    )
    (net (code "215") (name "/EXTEND_B29") (class "Default")
      (node (ref "U1") (pin "R5") (pinfunction "IO_L40P_3_R5") (pintype "bidirectional"))
    )
    (net (code "216") (name "/EXTEND_B30") (class "Default")
      (node (ref "U1") (pin "T5") (pinfunction "IO_L42P_3_T5") (pintype "bidirectional"))
    )
    (net (code "217") (name "/EXTEND_B31") (class "Default")
      (node (ref "U1") (pin "U4") (pinfunction "IO_L42N_3_U4") (pintype "bidirectional"))
    )
    (net (code "218") (name "/EXTEND_B32") (class "Default")
      (node (ref "U1") (pin "V2") (pinfunction "IO_L47N_3_V2") (pintype "bidirectional"))
    )
    (net (code "219") (name "/EXTEND_B33") (class "Default")
      (node (ref "U1") (pin "U7") (pinfunction "IO_L56P_3_U7") (pintype "bidirectional"))
    )
    (net (code "220") (name "/EXTEND_B34") (class "Default")
      (node (ref "U1") (pin "U8") (pinfunction "IO_L56N_3_U8") (pintype "bidirectional"))
    )
    (net (code "221") (name "/EXTEND_B35") (class "Default")
      (node (ref "U1") (pin "W3") (pinfunction "IO_L52P_3_W3") (pintype "bidirectional"))
    )
    (net (code "222") (name "/EXTEND_B36") (class "Default")
      (node (ref "U1") (pin "U9") (pinfunction "IO_L61P_3_U9") (pintype "bidirectional"))
    )
    (net (code "223") (name "/EXTEND_B37") (class "Default")
      (node (ref "U1") (pin "W6") (pinfunction "IO_L63N_3_W6") (pintype "bidirectional"))
    )
    (net (code "224") (name "/EXTEND_B38") (class "Default")
      (node (ref "U1") (pin "AA3") (pinfunction "IO_L55N_3_AA3") (pintype "bidirectional"))
    )
    (net (code "225") (name "/EXTEND_B39") (class "Default")
      (node (ref "U1") (pin "AC3") (pinfunction "IO_L64N_3_AC3") (pintype "bidirectional"))
    )
    (net (code "226") (name "/EXTEND_B40") (class "Default")
      (node (ref "U1") (pin "AC1") (pinfunction "IO_L60N_3_AC1") (pintype "bidirectional"))
    )
    (net (code "227") (name "/EXTEND_B41") (class "Default")
      (node (ref "U1") (pin "AD2") (pinfunction "IO_L65N_3_AD2") (pintype "bidirectional"))
    )
    (net (code "228") (name "/EXTEND_B42") (class "Default")
      (node (ref "U1") (pin "Y5") (pinfunction "IO_L57P_3_Y5") (pintype "bidirectional"))
    )
    (net (code "229") (name "/EXTEND_B43") (class "Default")
      (node (ref "U1") (pin "U5") (pinfunction "IO_L49P_3_U5") (pintype "bidirectional"))
    )
    (net (code "230") (name "/EXTEND_B44") (class "Default")
      (node (ref "U1") (pin "T7") (pinfunction "IO_L51P_3_T7") (pintype "bidirectional"))
    )
    (net (code "231") (name "/EXTEND_B45") (class "Default")
      (node (ref "U1") (pin "V7") (pinfunction "IO_L59P_3_V7") (pintype "bidirectional"))
    )
    (net (code "232") (name "/EXTEND_B46") (class "Default")
      (node (ref "U1") (pin "U11") (pinfunction "IO_L13N_2_U11") (pintype "bidirectional"))
    )
    (net (code "233") (name "/EXTEND_B47") (class "Default")
      (node (ref "U1") (pin "AA2") (pinfunction "IO_L55P_3_AA2") (pintype "bidirectional"))
    )
    (net (code "234") (name "/EXTEND_B48") (class "Default")
      (node (ref "U1") (pin "AB1") (pinfunction "IO_L60P_3_AB1") (pintype "bidirectional"))
    )
    (net (code "235") (name "/EXTEND_B49") (class "Default")
      (node (ref "U1") (pin "Y6") (pinfunction "IO_L57N_3_Y6") (pintype "bidirectional"))
    )
    (net (code "237") (name "/EXTEND_C0") (class "Default")
      (node (ref "U1") (pin "L24") (pinfunction "IO_L38P_1/A12_L24") (pintype "bidirectional"))
    )
    (net (code "238") (name "/EXTEND_C1") (class "Default")
      (node (ref "U1") (pin "L20") (pinfunction "IO_L53P_1_L20") (pintype "bidirectional"))
    )
    (net (code "239") (name "/EXTEND_C2") (class "Default")
      (node (ref "U1") (pin "J26") (pinfunction "IO_L43P_1/A18_J26") (pintype "bidirectional"))
    )
    (net (code "240") (name "/EXTEND_C3") (class "Default")
      (node (ref "U1") (pin "K18") (pinfunction "IO_L57N_1_K18") (pintype "bidirectional"))
    )
    (net (code "241") (name "/EXTEND_C4") (class "Default")
      (node (ref "U1") (pin "N18") (pinfunction "IO_L39P_1/A14_N18") (pintype "bidirectional"))
    )
    (net (code "242") (name "/EXTEND_C5") (class "Default")
      (node (ref "U1") (pin "N19") (pinfunction "IO_L34N_1/RHCLK7_N19") (pintype "bidirectional"))
    )
    (net (code "243") (name "/EXTEND_C6") (class "Default")
      (node (ref "U1") (pin "M20") (pinfunction "IO_L42N_1/A17_M20") (pintype "bidirectional"))
    )
    (net (code "244") (name "/EXTEND_C7") (class "Default")
      (node (ref "U1") (pin "L22") (pinfunction "IO_L50P_1_L22") (pintype "bidirectional"))
    )
    (net (code "245") (name "/EXTEND_C8") (class "Default")
      (node (ref "U1") (pin "K21") (pinfunction "IO_L50N_1_K21") (pintype "bidirectional"))
    )
    (net (code "246") (name "/EXTEND_C9") (class "Default")
      (node (ref "U1") (pin "K19") (pinfunction "IO_L57P_1_K19") (pintype "bidirectional"))
    )
    (net (code "247") (name "/EXTEND_C10") (class "Default")
      (node (ref "U1") (pin "G23") (pinfunction "IO_L51P_1_G23") (pintype "bidirectional"))
    )
    (net (code "248") (name "/EXTEND_C11") (class "Default")
      (node (ref "U1") (pin "F25") (pinfunction "IO_L54P_1_F25") (pintype "bidirectional"))
    )
    (net (code "249") (name "/EXTEND_C12") (class "Default")
      (node (ref "U1") (pin "E26") (pinfunction "IO_L60P_1_E26") (pintype "bidirectional"))
    )
    (net (code "250") (name "/EXTEND_C13") (class "Default")
      (node (ref "U1") (pin "D26") (pinfunction "IO_L60N_1_D26") (pintype "bidirectional"))
    )
    (net (code "251") (name "/EXTEND_C14") (class "Default")
      (node (ref "U1") (pin "C23") (pinfunction "IO_L06N_0_C23") (pintype "bidirectional"))
    )
    (net (code "252") (name "/EXTEND_C15") (class "Default")
      (node (ref "U1") (pin "B23") (pinfunction "IO_L07P_0_B23") (pintype "bidirectional"))
    )
    (net (code "253") (name "/EXTEND_C16") (class "Default")
      (node (ref "U1") (pin "D22") (pinfunction "IO_L05P_0_D22") (pintype "bidirectional"))
    )
    (net (code "254") (name "/EXTEND_C17") (class "Default")
      (node (ref "U1") (pin "C22") (pinfunction "IO_L05N_0_C22") (pintype "bidirectional"))
    )
    (net (code "255") (name "/EXTEND_C18") (class "Default")
      (node (ref "U1") (pin "J20") (pinfunction "IO_L59N_1_J20") (pintype "bidirectional"))
    )
    (net (code "256") (name "/EXTEND_C19") (class "Default")
      (node (ref "U1") (pin "G20") (pinfunction "IO_L01P_0_G20") (pintype "bidirectional"))
    )
    (net (code "257") (name "/EXTEND_C20") (class "Default")
      (node (ref "U1") (pin "J19") (pinfunction "IO_L59P_1_J19") (pintype "bidirectional"))
    )
    (net (code "258") (name "/EXTEND_C21") (class "Default")
      (node (ref "U1") (pin "B19") (pinfunction "IO_L15P_0_B19") (pintype "bidirectional"))
    )
    (net (code "259") (name "/EXTEND_C22") (class "Default")
      (node (ref "U1") (pin "C18") (pinfunction "IO_L17N_0_C18") (pintype "bidirectional"))
    )
    (net (code "260") (name "/EXTEND_C23") (class "Default")
      (node (ref "U1") (pin "D17") (pinfunction "IO_L21P_0_D17") (pintype "bidirectional"))
    )
    (net (code "261") (name "/EXTEND_C24") (class "Default")
      (node (ref "U1") (pin "D16") (pinfunction "IO_L22P_0_D16") (pintype "bidirectional"))
    )
    (net (code "262") (name "/EXTEND_C25") (class "Default")
      (node (ref "U1") (pin "C16") (pinfunction "IO_L21N_0_C16") (pintype "bidirectional"))
    )
    (net (code "263") (name "/EXTEND_C26") (class "Default")
      (node (ref "U1") (pin "K16") (pinfunction "IO_L12N_0_K16") (pintype "bidirectional"))
    )
    (net (code "264") (name "/EXTEND_C27") (class "Default")
      (node (ref "U1") (pin "C15") (pinfunction "IO_L22N_0_C15") (pintype "bidirectional"))
    )
    (net (code "265") (name "/EXTEND_C28") (class "Default")
      (node (ref "U1") (pin "J14") (pinfunction "IO_L25N_0/GCLK5_J14") (pintype "bidirectional"))
    )
    (net (code "266") (name "/EXTEND_C29") (class "Default")
      (node (ref "U1") (pin "F13") (pinfunction "IO_L27P_0/GCLK8_F13") (pintype "bidirectional"))
    )
    (net (code "267") (name "/EXTEND_C30") (class "Default")
      (node (ref "U1") (pin "G12") (pinfunction "IO_L35P_0_G12") (pintype "bidirectional"))
    )
    (net (code "268") (name "/EXTEND_C31") (class "Default")
      (node (ref "U1") (pin "Y13") (pinfunction "IO_L25N_2/GCLK13_Y13") (pintype "bidirectional"))
    )
    (net (code "269") (name "/EXTEND_C32") (class "Default")
      (node (ref "U1") (pin "J12") (pinfunction "IO_L39P_0_J12") (pintype "bidirectional"))
    )
    (net (code "270") (name "/EXTEND_C33") (class "Default")
      (node (ref "U1") (pin "D11") (pinfunction "IO_L32N_0/VREF_0_D11") (pintype "bidirectional"))
    )
    (net (code "271") (name "/EXTEND_C34") (class "Default")
      (node (ref "U1") (pin "B10") (pinfunction "IO_L33N_0_B10") (pintype "bidirectional"))
    )
    (net (code "272") (name "/EXTEND_C35") (class "Default")
      (node (ref "U1") (pin "E10") (pinfunction "IO_L37P_0_E10") (pintype "bidirectional"))
    )
    (net (code "273") (name "/EXTEND_C36") (class "Default")
      (node (ref "U1") (pin "B9") (pinfunction "IO_L36N_0_B9") (pintype "bidirectional"))
    )
    (net (code "274") (name "/EXTEND_C37") (class "Default")
      (node (ref "U1") (pin "H9") (pinfunction "IO_L47N_0_H9") (pintype "bidirectional"))
    )
    (net (code "275") (name "/EXTEND_C38") (class "Default")
      (node (ref "U1") (pin "D8") (pinfunction "IO_L40N_0_D8") (pintype "bidirectional"))
    )
    (net (code "276") (name "/EXTEND_C39") (class "Default")
      (node (ref "U1") (pin "E7") (pinfunction "IO_L48N_0_E7") (pintype "bidirectional"))
    )
    (net (code "277") (name "/EXTEND_C40") (class "Default")
      (node (ref "U1") (pin "K12") (pinfunction "IO_L39N_0_K12") (pintype "bidirectional"))
    )
    (net (code "278") (name "/EXTEND_C41") (class "Default")
      (node (ref "U1") (pin "C7") (pinfunction "IO_L42N_0_C7") (pintype "bidirectional"))
    )
    (net (code "279") (name "/EXTEND_C42") (class "Default")
      (node (ref "U1") (pin "A10") (pinfunction "IO_L33P_0_A10") (pintype "bidirectional"))
    )
    (net (code "280") (name "/EXTEND_C43") (class "Default")
      (node (ref "U1") (pin "C6") (pinfunction "IO_L41N_0_C6") (pintype "bidirectional"))
    )
    (net (code "281") (name "/EXTEND_C44") (class "Default")
      (node (ref "U1") (pin "D10") (pinfunction "IO_L34N_0_D10") (pintype "bidirectional"))
    )
    (net (code "282") (name "/EXTEND_C45") (class "Default")
      (node (ref "U1") (pin "C5") (pinfunction "IO_L44P_0_C5") (pintype "bidirectional"))
    )
    (net (code "283") (name "/EXTEND_C46") (class "Default")
      (node (ref "U1") (pin "A9") (pinfunction "IO_L36P_0_A9") (pintype "bidirectional"))
    )
    (net (code "284") (name "/EXTEND_C47") (class "Default")
      (node (ref "U1") (pin "A4") (pinfunction "IO_L45P_0_A4") (pintype "bidirectional"))
    )
    (net (code "285") (name "/EXTEND_C48") (class "Default")
      (node (ref "U1") (pin "C8") (pinfunction "IO_L40P_0_C8") (pintype "bidirectional"))
    )
    (net (code "286") (name "/EXTEND_C49") (class "Default")
      (node (ref "U1") (pin "B8") (pinfunction "IO_L38N_0_B8") (pintype "bidirectional"))
    )
    (net (code "288") (name "/FPGA_CCLK") (class "Default")
      (node (ref "R20") (pin "1") (pinfunction "1_1") (pintype "passive"))
    )
    (net (code "289") (name "/FPGA_CCLK#") (class "Default")
      (node (ref "R20") (pin "2") (pinfunction "2_2") (pintype "passive"))
      (node (ref "U1") (pin "AE24") (pinfunction "IO_L52N_2/CCLK_AE24") (pintype "bidirectional"))
    )
    (net (code "290") (name "/FPGA_CLK") (class "Default")
      (node (ref "U1") (pin "AA13") (pinfunction "IO_L25P_2/GCLK12_AA13") (pintype "bidirectional"))
    )
    (net (code "291") (name "/FPGA_CLK1") (class "Default")
      (node (ref "U1") (pin "B13") (pinfunction "IO_L28P_0/GCLK10_B13") (pintype "bidirectional"))
    )
    (net (code "292") (name "/FPGA_DIN") (class "Default")
      (node (ref "U1") (pin "AF24") (pinfunction "IO_L52P_2/D0/DIN/MISO_AF24") (pintype "bidirectional"))
    )
    (net (code "293") (name "/FPGA_DONE") (class "Default")
      (node (ref "NT6") (pin "2") (pinfunction "Net2_2") (pintype "passive"))
      (node (ref "R22") (pin "1") (pinfunction "1_1") (pintype "passive"))
      (node (ref "R4") (pin "1") (pinfunction "1_1") (pintype "passive"))
    )
    (net (code "294") (name "/FPGA_ID0") (class "Default")
      (node (ref "NT2") (pin "1") (pinfunction "Net1_1") (pintype "passive"))
    )
    (net (code "295") (name "/FPGA_ID1") (class "Default")
      (node (ref "NT3") (pin "1") (pinfunction "Net1_1") (pintype "passive"))
    )
    (net (code "296") (name "/FPGA_ID2") (class "Default")
      (node (ref "NT4") (pin "1") (pinfunction "Net1_1") (pintype "passive"))
    )
    (net (code "297") (name "/FPGA_ID3") (class "Default")
      (node (ref "NT5") (pin "1") (pinfunction "Net1_1") (pintype "passive"))
    )
    (net (code "298") (name "/FPGA_INIT") (class "Default")
      (node (ref "R3") (pin "1") (pinfunction "1_1") (pintype "passive"))
      (node (ref "U1") (pin "AA15") (pinfunction "IO_L34P_2/INIT_B_AA15") (pintype "bidirectional"))
    )
    (net (code "299") (name "/FPGA_M0") (class "Default")
      (node (ref "R23") (pin "1") (pinfunction "1_1") (pintype "passive"))
    )
    (net (code "300") (name "/FPGA_M0#") (class "Default")
      (node (ref "R23") (pin "2") (pinfunction "2_2") (pintype "passive"))
      (node (ref "U1") (pin "AD4") (pinfunction "IO_L01N_2/M0_AD4") (pintype "bidirectional"))
    )
    (net (code "301") (name "/FPGA_M1") (class "Default")
      (node (ref "R18") (pin "1") (pinfunction "1_1") (pintype "passive"))
    )
    (net (code "302") (name "/FPGA_M1#") (class "Default")
      (node (ref "R18") (pin "2") (pinfunction "2_2") (pintype "passive"))
      (node (ref "U1") (pin "AC4") (pinfunction "IO_L01P_2/M1_AC4") (pintype "bidirectional"))
    )
    (net (code "303") (name "/FPGA_M2") (class "Default")
      (node (ref "R14") (pin "1") (pinfunction "1_1") (pintype "passive"))
    )
    (net (code "304") (name "/FPGA_M2#") (class "Default")
      (node (ref "R14") (pin "2") (pinfunction "2_2") (pintype "passive"))
      (node (ref "U1") (pin "Y7") (pinfunction "IO_L02P_2/M2_Y7") (pintype "bidirectional"))
    )
    (net (code "306") (name "/FPGA_PROGRAM") (class "Default")
      (node (ref "R1") (pin "1") (pinfunction "1_1") (pintype "passive"))
      (node (ref "R24") (pin "1") (pinfunction "1_1") (pintype "passive"))
    )
    (net (code "309") (name "/FPGA_TCK") (class "Default")
      (node (ref "R9") (pin "1") (pinfunction "1_1") (pintype "passive"))
    )
    (net (code "310") (name "/FPGA_TDI") (class "Default")
      (node (ref "R12") (pin "1") (pinfunction "1_1") (pintype "passive"))
    )
    (net (code "311") (name "/FPGA_TDO") (class "Default")
      (node (ref "R10") (pin "1") (pinfunction "1_1") (pintype "passive"))
      (node (ref "R2") (pin "1") (pinfunction "1_1") (pintype "passive"))
    )
    (net (code "312") (name "/FPGA_TMS") (class "Default")
      (node (ref "R8") (pin "1") (pinfunction "1_1") (pintype "passive"))
    )
    (net (code "313") (name "/IO0") (class "Default")
      (node (ref "U1") (pin "AF3") (pinfunction "IO_L06N_2_AF3") (pintype "bidirectional"))
    )
    (net (code "314") (name "/IO1") (class "Default")
      (node (ref "U1") (pin "AF5") (pinfunction "IO_L10P_2_AF5") (pintype "bidirectional"))
    )
    (net (code "315") (name "/IO2") (class "Default")
      (node (ref "U1") (pin "AD6") (pinfunction "IO_L08N_2_AD6") (pintype "bidirectional"))
    )
    (net (code "316") (name "/IO3") (class "Default")
      (node (ref "U1") (pin "AE6") (pinfunction "IO_L10N_2_AE6") (pintype "bidirectional"))
    )
    (net (code "317") (name "/IO4") (class "Default")
      (node (ref "U1") (pin "V8") (pinfunction "IO_L61N_3_V8") (pintype "bidirectional"))
    )
    (net (code "318") (name "/IO5") (class "Default")
      (node (ref "U1") (pin "AE7") (pinfunction "IO_L11N_2_AE7") (pintype "bidirectional"))
    )
    (net (code "319") (name "/IO6") (class "Default")
      (node (ref "U1") (pin "AA7") (pinfunction "IO_L02N_2/CSO_B_AA7") (pintype "bidirectional"))
    )
    (net (code "320") (name "/IO7") (class "Default")
      (node (ref "U1") (pin "AC2") (pinfunction "IO_L64P_3_AC2") (pintype "bidirectional"))
    )
    (net (code "321") (name "/IO8") (class "Default")
      (node (ref "U1") (pin "AB9") (pinfunction "IO_L15P_2_AB9") (pintype "bidirectional"))
    )
    (net (code "322") (name "/IO9") (class "Default")
      (node (ref "U1") (pin "AC9") (pinfunction "IO_L15N_2_AC9") (pintype "bidirectional"))
    )
    (net (code "323") (name "/IO10") (class "Default")
      (node (ref "U1") (pin "AA10") (pinfunction "IO_L12N_2_AA10") (pintype "bidirectional"))
    )
    (net (code "324") (name "/IO11") (class "Default")
      (node (ref "U1") (pin "AE10") (pinfunction "IO_L22P_2/D7_AE10") (pintype "bidirectional"))
    )
    (net (code "325") (name "/IO12") (class "Default")
      (node (ref "U1") (pin "AF10") (pinfunction "IO_L22N_2/D6_AF10") (pintype "bidirectional"))
    )
    (net (code "326") (name "/IO13") (class "Default")
      (node (ref "U1") (pin "AC11") (pinfunction "IO_L23N_2_AC11") (pintype "bidirectional"))
    )
    (net (code "327") (name "/IO14") (class "Default")
      (node (ref "U1") (pin "AC12") (pinfunction "IO_L21N_2_AC12") (pintype "bidirectional"))
    )
    (net (code "328") (name "/IO15") (class "Default")
      (node (ref "U1") (pin "AE12") (pinfunction "IO_L24N_2/D4_AE12") (pintype "bidirectional"))
    )
    (net (code "329") (name "/IO16") (class "Default")
      (node (ref "U1") (pin "W13") (pinfunction "IO_L20N_2_W13") (pintype "bidirectional"))
    )
    (net (code "330") (name "/IO17") (class "Default")
      (node (ref "U1") (pin "AE13") (pinfunction "IO_L26N_2/GCLK15_AE13") (pintype "bidirectional"))
    )
    (net (code "331") (name "/IO18") (class "Default")
      (node (ref "U1") (pin "AE14") (pinfunction "IO_L28N_2/GCLK3_AE14") (pintype "bidirectional"))
    )
    (net (code "332") (name "/IO19") (class "Default")
      (node (ref "U1") (pin "AF14") (pinfunction "IO_L28P_2/GCLK2_AF14") (pintype "bidirectional"))
    )
    (net (code "333") (name "/IO20") (class "Default")
      (node (ref "U1") (pin "AB15") (pinfunction "IO_L30N_2/MOSI/CSI_B_AB15") (pintype "bidirectional"))
    )
    (net (code "334") (name "/IO21") (class "Default")
      (node (ref "U1") (pin "V15") (pinfunction "IO_L35P_2_V15") (pintype "bidirectional"))
    )
    (net (code "335") (name "/IO22") (class "Default")
      (node (ref "U1") (pin "U15") (pinfunction "IO_L35N_2_U15") (pintype "bidirectional"))
    )
    (net (code "336") (name "/IO23") (class "Default")
      (node (ref "U1") (pin "AF18") (pinfunction "IO_L36P_2/D2_AF18") (pintype "bidirectional"))
    )
    (net (code "337") (name "/IO24") (class "Default")
      (node (ref "U1") (pin "Y17") (pinfunction "IO_L43N_2_Y17") (pintype "bidirectional"))
    )
    (net (code "338") (name "/IO25") (class "Default")
      (node (ref "U1") (pin "U18") (pinfunction "IO_L12N_1_U18") (pintype "bidirectional"))
    )
    (net (code "339") (name "/IO26") (class "Default")
      (node (ref "U1") (pin "AD19") (pinfunction "IO_L40P_2_AD19") (pintype "bidirectional"))
    )
    (net (code "340") (name "/IO27") (class "Default")
      (node (ref "U1") (pin "Y20") (pinfunction "IO_L01P_1/HDC_Y20") (pintype "bidirectional"))
    )
    (net (code "341") (name "/IO28") (class "Default")
      (node (ref "U1") (pin "W20") (pinfunction "IO_L04P_1_W20") (pintype "bidirectional"))
    )
    (net (code "342") (name "/IO29") (class "Default")
      (node (ref "U1") (pin "AD21") (pinfunction "IO_L44N_2_AD21") (pintype "bidirectional"))
    )
    (net (code "343") (name "/IO30") (class "Default")
      (node (ref "U1") (pin "Y21") (pinfunction "IO_L01N_1/LDC2_Y21") (pintype "bidirectional"))
    )
    (net (code "344") (name "/IO31") (class "Default")
      (node (ref "U1") (pin "AE23") (pinfunction "IO_L48N_2_AE23") (pintype "bidirectional"))
    )
    (net (code "345") (name "/IO32") (class "Default")
      (node (ref "U1") (pin "AC23") (pinfunction "IO_L03P_1/A0_AC23") (pintype "bidirectional"))
    )
    (net (code "346") (name "/IO33") (class "Default")
      (node (ref "U1") (pin "AB23") (pinfunction "IO_L07P_1_AB23") (pintype "bidirectional"))
    )
    (net (code "347") (name "/IO34") (class "Default")
      (node (ref "U1") (pin "AC24") (pinfunction "IO_L03N_1/A1_AC24") (pintype "bidirectional"))
    )
    (net (code "348") (name "/IO35") (class "Default")
      (node (ref "U1") (pin "AF25") (pinfunction "IO_L51P_2_AF25") (pintype "bidirectional"))
    )
    (net (code "349") (name "/KBCLOCK") (class "Default")
      (node (ref "U1") (pin "E15") (pinfunction "IO_L20N_0/VREF_0_E15") (pintype "bidirectional"))
    )
    (net (code "350") (name "/KBDATA") (class "Default")
      (node (ref "U1") (pin "F15") (pinfunction "IO_L20P_0_F15") (pintype "bidirectional"))
    )
    (net (code "351") (name "/LED0") (class "Default")
      (node (ref "U1") (pin "AB7") (pinfunction "IO_L14N_2_AB7") (pintype "bidirectional"))
    )
    (net (code "352") (name "/LED1") (class "Default")
      (node (ref "U1") (pin "AD7") (pinfunction "IO_L11P_2_AD7") (pintype "bidirectional"))
    )
    (net (code "353") (name "/LED2") (class "Default")
      (node (ref "U1") (pin "AE8") (pinfunction "IO_L18P_2_AE8") (pintype "bidirectional"))
    )
    (net (code "354") (name "/LED3") (class "Default")
      (node (ref "U1") (pin "AF8") (pinfunction "IO_L18N_2_AF8") (pintype "bidirectional"))
    )
    (net (code "355") (name "/LED4") (class "Default")
      (node (ref "U1") (pin "Y10") (pinfunction "IO_L12P_2_Y10") (pintype "bidirectional"))
    )
    (net (code "356") (name "/LED5") (class "Default")
      (node (ref "U1") (pin "V11") (pinfunction "IO_L13P_2_V11") (pintype "bidirectional"))
    )
    (net (code "357") (name "/LED6") (class "Default")
      (node (ref "U1") (pin "V12") (pinfunction "IO_L16P_2_V12") (pintype "bidirectional"))
    )
    (net (code "358") (name "/LED7") (class "Default")
      (node (ref "U1") (pin "Y12") (pinfunction "IO_L17P_2/RDWR_B_Y12") (pintype "bidirectional"))
    )
    (net (code "360") (name "/MOUSECLOCK") (class "Default")
      (node (ref "U1") (pin "E17") (pinfunction "IO_L13N_0_E17") (pintype "bidirectional"))
    )
    (net (code "361") (name "/MOUSEDATA") (class "Default")
      (node (ref "U1") (pin "C17") (pinfunction "IO_L19P_0_C17") (pintype "bidirectional"))
    )
    (net (code "362") (name "/NEXUS_TCK") (class "Default")
      (node (ref "U1") (pin "A14") (pinfunction "IO_L26N_0/GCLK7_A14") (pintype "bidirectional"))
    )
    (net (code "363") (name "/NEXUS_TDI") (class "Default")
      (node (ref "U1") (pin "R18") (pinfunction "IO_L27P_1/A6_R18") (pintype "bidirectional"))
    )
    (net (code "364") (name "/NEXUS_TDO") (class "Default")
      (node (ref "U1") (pin "D24") (pinfunction "IO_L61N_1_D24") (pintype "bidirectional"))
    )
    (net (code "365") (name "/NEXUS_TMS") (class "Default")
      (node (ref "U1") (pin "P23") (pinfunction "IO_L33P_1/RHCLK4_P23") (pintype "bidirectional"))
    )
    (net (code "367") (name "/ONE_WIRE_DB_PB") (class "Default")
      (node (ref "U1") (pin "AC8") (pinfunction "IO_L14P_2_AC8") (pintype "bidirectional"))
    )
    (net (code "371") (name "/PROG_B") (class "Default")
      (node (ref "R24") (pin "2") (pinfunction "2_2") (pintype "passive"))
    )
    (net (code "372") (name "/REF_CLK") (class "Default")
      (node (ref "U1") (pin "Y14") (pinfunction "IO_L27P_2/GCLK0_Y14") (pintype "bidirectional"))
    )
    (net (code "373") (name "/RS232_CTS") (class "Default")
      (node (ref "U1") (pin "A15") (pinfunction "IO_L23N_0_A15") (pintype "bidirectional"))
    )
    (net (code "374") (name "/RS232_RTS") (class "Default")
      (node (ref "U1") (pin "E12") (pinfunction "IO_L31P_0_E12") (pintype "bidirectional"))
    )
    (net (code "375") (name "/RS232_RX") (class "Default")
      (node (ref "U1") (pin "B15") (pinfunction "IO_L23P_0_B15") (pintype "bidirectional"))
    )
    (net (code "376") (name "/RS232_TX") (class "Default")
      (node (ref "U1") (pin "G13") (pinfunction "IO_L27N_0/GCLK9_G13") (pintype "bidirectional"))
    )
    (net (code "377") (name "/SCL") (class "Default")
      (node (ref "U1") (pin "W7") (pinfunction "IO_L63P_3_W7") (pintype "bidirectional"))
    )
    (net (code "378") (name "/SDA") (class "Default")
      (node (ref "U1") (pin "AF4") (pinfunction "IO_L07N_2_AF4") (pintype "bidirectional"))
    )
    (net (code "379") (name "/SLEEP_N") (class "Default")
      (node (ref "U3") (pin "2") (pinfunction "A_2") (pintype "input"))
    )
    (net (code "380") (name "/SPI_CLK") (class "Default")
      (node (ref "U1") (pin "D13") (pinfunction "IO_L30P_0_D13") (pintype "bidirectional"))
    )
    (net (code "381") (name "/SPI_DIN") (class "Default")
      (node (ref "U1") (pin "A12") (pinfunction "IO_L29P_0_A12") (pintype "bidirectional"))
    )
    (net (code "382") (name "/SPI_DOUT") (class "Default")
      (node (ref "U1") (pin "E14") (pinfunction "IO_L24P_0_E14") (pintype "bidirectional"))
    )
    (net (code "383") (name "/SPI_MODE") (class "Default")
      (node (ref "U1") (pin "G15") (pinfunction "IO_L16P_0_G15") (pintype "bidirectional"))
    )
    (net (code "384") (name "/SPI_SEL") (class "Default")
      (node (ref "U1") (pin "K14") (pinfunction "IO_L25P_0/GCLK4_K14") (pintype "bidirectional"))
    )
    (net (code "385") (name "/SRAM1_A0") (class "Default")
      (node (ref "U1") (pin "AB18") (pinfunction "IO_L47P_2_AB18") (pintype "bidirectional"))
    )
    (net (code "386") (name "/SRAM1_A1") (class "Default")
      (node (ref "U1") (pin "V19") (pinfunction "IO_L08N_1_V19") (pintype "bidirectional"))
    )
    (net (code "387") (name "/SRAM1_A2") (class "Default")
      (node (ref "U1") (pin "AE21") (pinfunction "IO_L44P_2_AE21") (pintype "bidirectional"))
    )
    (net (code "388") (name "/SRAM1_A3") (class "Default")
      (node (ref "U1") (pin "AC22") (pinfunction "IO_2_AC22") (pintype "bidirectional"))
    )
    (net (code "389") (name "/SRAM1_A4") (class "Default")
      (node (ref "U1") (pin "AE25") (pinfunction "IO_L51N_2_AE25") (pintype "bidirectional"))
    )
    (net (code "390") (name "/SRAM1_A5") (class "Default")
      (node (ref "U1") (pin "U16") (pinfunction "IO_L42N_2_U16") (pintype "bidirectional"))
    )
    (net (code "391") (name "/SRAM1_A6") (class "Default")
      (node (ref "U1") (pin "AA18") (pinfunction "IO_L47N_2_AA18") (pintype "bidirectional"))
    )
    (net (code "392") (name "/SRAM1_A7") (class "Default")
      (node (ref "U1") (pin "AF19") (pinfunction "IO_L37P_2_AF19") (pintype "bidirectional"))
    )
    (net (code "393") (name "/SRAM1_A8") (class "Default")
      (node (ref "U1") (pin "AF20") (pinfunction "IO_L39P_2_AF20") (pintype "bidirectional"))
    )
    (net (code "394") (name "/SRAM1_A9") (class "Default")
      (node (ref "U1") (pin "U19") (pinfunction "IO_L12P_1_U19") (pintype "bidirectional"))
    )
    (net (code "395") (name "/SRAM1_A10") (class "Default")
      (node (ref "U1") (pin "AF23") (pinfunction "IO_L48P_2_AF23") (pintype "bidirectional"))
    )
    (net (code "396") (name "/SRAM1_A11") (class "Default")
      (node (ref "U1") (pin "AD20") (pinfunction "IO_L41P_2_AD20") (pintype "bidirectional"))
    )
    (net (code "397") (name "/SRAM1_A12") (class "Default")
      (node (ref "U1") (pin "AC19") (pinfunction "IO_L40N_2_AC19") (pintype "bidirectional"))
    )
    (net (code "398") (name "/SRAM1_A13") (class "Default")
      (node (ref "U1") (pin "W17") (pinfunction "IO_L46P_2_W17") (pintype "bidirectional"))
    )
    (net (code "399") (name "/SRAM1_A14") (class "Default")
      (node (ref "U1") (pin "AE18") (pinfunction "IO_L36N_2/D1_AE18") (pintype "bidirectional"))
    )
    (net (code "400") (name "/SRAM1_A15") (class "Default")
      (node (ref "U1") (pin "AA17") (pinfunction "IO_L43P_2_AA17") (pintype "bidirectional"))
    )
    (net (code "401") (name "/SRAM1_A16") (class "Default")
      (node (ref "U1") (pin "AB16") (pinfunction "IO_L38N_2_AB16") (pintype "bidirectional"))
    )
    (net (code "402") (name "/SRAM1_A17") (class "Default")
      (node (ref "U1") (pin "AC16") (pinfunction "IO_L38P_2_AC16") (pintype "bidirectional"))
    )
    (net (code "403") (name "/SRAM1_A18") (class "Default")
      (node (ref "U1") (pin "W15") (pinfunction "IO_L31N_2_W15") (pintype "bidirectional"))
    )
    (net (code "405") (name "/SRAM1_D0") (class "Default")
      (node (ref "U1") (pin "AC14") (pinfunction "IO_L29N_2_AC14") (pintype "bidirectional"))
    )
    (net (code "406") (name "/SRAM1_D1") (class "Default")
      (node (ref "U1") (pin "AE17") (pinfunction "IO_L33P_2_AE17") (pintype "bidirectional"))
    )
    (net (code "407") (name "/SRAM1_D2") (class "Default")
      (node (ref "U1") (pin "AD17") (pinfunction "IO_L33N_2_AD17") (pintype "bidirectional"))
    )
    (net (code "408") (name "/SRAM1_D3") (class "Default")
      (node (ref "U1") (pin "V17") (pinfunction "IO_L46N_2_V17") (pintype "bidirectional"))
    )
    (net (code "409") (name "/SRAM1_D4") (class "Default")
      (node (ref "U1") (pin "V18") (pinfunction "IO_L08P_1_V18") (pintype "bidirectional"))
    )
    (net (code "410") (name "/SRAM1_D5") (class "Default")
      (node (ref "U1") (pin "AC20") (pinfunction "IO_L41N_2_AC20") (pintype "bidirectional"))
    )
    (net (code "411") (name "/SRAM1_D6") (class "Default")
      (node (ref "U1") (pin "AC21") (pinfunction "IO_L45N_2_AC21") (pintype "bidirectional"))
    )
    (net (code "412") (name "/SRAM1_D7") (class "Default")
      (node (ref "U1") (pin "AD22") (pinfunction "IO_L45P_2_AD22") (pintype "bidirectional"))
    )
    (net (code "413") (name "/SRAM1_D8") (class "Default")
      (node (ref "U1") (pin "AD15") (pinfunction "IO_L32P_2/AWAKE_AD15") (pintype "bidirectional"))
    )
    (net (code "414") (name "/SRAM1_D9") (class "Default")
      (node (ref "U1") (pin "V14") (pinfunction "IO_L31P_2_V14") (pintype "bidirectional"))
    )
    (net (code "415") (name "/SRAM1_D10") (class "Default")
      (node (ref "U1") (pin "AE15") (pinfunction "IO_L32N_2/DOUT_AE15") (pintype "bidirectional"))
    )
    (net (code "416") (name "/SRAM1_D11") (class "Default")
      (node (ref "U1") (pin "AE26") (pinfunction "IO_L02P_1/LDC1_AE26") (pintype "bidirectional"))
    )
    (net (code "417") (name "/SRAM1_D12") (class "Default")
      (node (ref "U1") (pin "AA22") (pinfunction "IO_L09P_1_AA22") (pintype "bidirectional"))
    )
    (net (code "418") (name "/SRAM1_D13") (class "Default")
      (node (ref "U1") (pin "AE20") (pinfunction "IO_L39N_2_AE20") (pintype "bidirectional"))
    )
    (net (code "419") (name "/SRAM1_D14") (class "Default")
      (node (ref "U1") (pin "AE19") (pinfunction "IO_L37N_2_AE19") (pintype "bidirectional"))
    )
    (net (code "420") (name "/SRAM1_D15") (class "Default")
      (node (ref "U1") (pin "V13") (pinfunction "IO_L20P_2_V13") (pintype "bidirectional"))
    )
    (net (code "422") (name "/SRAM1_NBHE") (class "Default")
      (node (ref "U1") (pin "AC15") (pinfunction "IO_L30P_2_AC15") (pintype "bidirectional"))
    )
    (net (code "423") (name "/SRAM1_NBLE") (class "Default")
      (node (ref "U1") (pin "AA14") (pinfunction "IO_L27N_2/GCLK1_AA14") (pintype "bidirectional"))
    )
    (net (code "424") (name "/SRAM1_NCS") (class "Default")
      (node (ref "U1") (pin "AD14") (pinfunction "IO_L29P_2_AD14") (pintype "bidirectional"))
    )
    (net (code "425") (name "/SRAM1_NOE") (class "Default")
      (node (ref "U1") (pin "Y15") (pinfunction "IO_L34N_2/D3_Y15") (pintype "bidirectional"))
    )
    (net (code "426") (name "/SRAM1_NWE") (class "Default")
      (node (ref "U1") (pin "V16") (pinfunction "IO_L42P_2_V16") (pintype "bidirectional"))
    )
    (net (code "427") (name "/SRAM2_A0") (class "Default")
      (node (ref "U1") (pin "U21") (pinfunction "IO_L14P_1_U21") (pintype "bidirectional"))
    )
    (net (code "428") (name "/SRAM2_A1") (class "Default")
      (node (ref "U1") (pin "T18") (pinfunction "IO_L17P_1_T18") (pintype "bidirectional"))
    )
    (net (code "429") (name "/SRAM2_A2") (class "Default")
      (node (ref "U1") (pin "R21") (pinfunction "IO_L25P_1/A2_R21") (pintype "bidirectional"))
    )
    (net (code "430") (name "/SRAM2_A3") (class "Default")
      (node (ref "U1") (pin "R22") (pinfunction "IO_L25N_1/A3_R22") (pintype "bidirectional"))
    )
    (net (code "431") (name "/SRAM2_A4") (class "Default")
      (node (ref "U1") (pin "AC25") (pinfunction "IO_L05N_1_AC25") (pintype "bidirectional"))
    )
    (net (code "432") (name "/SRAM2_A5") (class "Default")
      (node (ref "U1") (pin "T23") (pinfunction "IO_L26P_1/A4_T23") (pintype "bidirectional"))
    )
    (net (code "433") (name "/SRAM2_A6") (class "Default")
      (node (ref "U1") (pin "R20") (pinfunction "IO_L22N_1_R20") (pintype "bidirectional"))
    )
    (net (code "434") (name "/SRAM2_A7") (class "Default")
      (node (ref "U1") (pin "R25") (pinfunction "IO_L29P_1/A8_R25") (pintype "bidirectional"))
    )
    (net (code "435") (name "/SRAM2_A8") (class "Default")
      (node (ref "U1") (pin "P18") (pinfunction "IO_L34P_1/IRDY1/RHCLK6_P18") (pintype "bidirectional"))
    )
    (net (code "436") (name "/SRAM2_A9") (class "Default")
      (node (ref "U1") (pin "P22") (pinfunction "IO_L37P_1_P22") (pintype "bidirectional"))
    )
    (net (code "437") (name "/SRAM2_A10") (class "Default")
      (node (ref "U1") (pin "P25") (pinfunction "IO_L31N_1/TRDY1/RHCLK3_P25") (pintype "bidirectional"))
    )
    (net (code "438") (name "/SRAM2_A11") (class "Default")
      (node (ref "U1") (pin "P21") (pinfunction "IO_L30P_1/RHCLK0_P21") (pintype "bidirectional"))
    )
    (net (code "439") (name "/SRAM2_A12") (class "Default")
      (node (ref "U1") (pin "R19") (pinfunction "IO_L22P_1_R19") (pintype "bidirectional"))
    )
    (net (code "440") (name "/SRAM2_A13") (class "Default")
      (node (ref "U1") (pin "R26") (pinfunction "IO_L29N_1/A9_R26") (pintype "bidirectional"))
    )
    (net (code "441") (name "/SRAM2_A14") (class "Default")
      (node (ref "U1") (pin "T24") (pinfunction "IO_L26N_1/A5_T24") (pintype "bidirectional"))
    )
    (net (code "442") (name "/SRAM2_A15") (class "Default")
      (node (ref "U1") (pin "AD25") (pinfunction "IO_L02N_1/LDC0_AD25") (pintype "bidirectional"))
    )
    (net (code "443") (name "/SRAM2_A16") (class "Default")
      (node (ref "U1") (pin "AD26") (pinfunction "IO_L05P_1_AD26") (pintype "bidirectional"))
    )
    (net (code "444") (name "/SRAM2_A17") (class "Default")
      (node (ref "U1") (pin "Y23") (pinfunction "IO_L13N_1_Y23") (pintype "bidirectional"))
    )
    (net (code "445") (name "/SRAM2_A18") (class "Default")
      (node (ref "U1") (pin "T20") (pinfunction "IO_L14N_1_T20") (pintype "bidirectional"))
    )
    (net (code "447") (name "/SRAM2_D0") (class "Default")
      (node (ref "U1") (pin "AA23") (pinfunction "IO_L09N_1_AA23") (pintype "bidirectional"))
    )
    (net (code "448") (name "/SRAM2_D1") (class "Default")
      (node (ref "U1") (pin "AA25") (pinfunction "IO_L11N_1_AA25") (pintype "bidirectional"))
    )
    (net (code "449") (name "/SRAM2_D2") (class "Default")
      (node (ref "U1") (pin "Y24") (pinfunction "IO_L15P_1_Y24") (pintype "bidirectional"))
    )
    (net (code "450") (name "/SRAM2_D3") (class "Default")
      (node (ref "U1") (pin "Y25") (pinfunction "IO_L15N_1_Y25") (pintype "bidirectional"))
    )
    (net (code "451") (name "/SRAM2_D4") (class "Default")
      (node (ref "U1") (pin "V22") (pinfunction "IO_L18N_1_V22") (pintype "bidirectional"))
    )
    (net (code "452") (name "/SRAM2_D5") (class "Default")
      (node (ref "U1") (pin "V24") (pinfunction "IO_L19P_1_V24") (pintype "bidirectional"))
    )
    (net (code "453") (name "/SRAM2_D6") (class "Default")
      (node (ref "U1") (pin "V25") (pinfunction "IO_L19N_1_V25") (pintype "bidirectional"))
    )
    (net (code "454") (name "/SRAM2_D7") (class "Default")
      (node (ref "U1") (pin "U22") (pinfunction "IO_L21N_1_U22") (pintype "bidirectional"))
    )
    (net (code "455") (name "/SRAM2_D8") (class "Default")
      (node (ref "U1") (pin "U20") (pinfunction "IO_L10N_1_U20") (pintype "bidirectional"))
    )
    (net (code "456") (name "/SRAM2_D9") (class "Default")
      (node (ref "U1") (pin "U24") (pinfunction "IO_L23N_1/VREF_1_U24") (pintype "bidirectional"))
    )
    (net (code "457") (name "/SRAM2_D10") (class "Default")
      (node (ref "U1") (pin "U23") (pinfunction "IO_L23P_1_U23") (pintype "bidirectional"))
    )
    (net (code "458") (name "/SRAM2_D11") (class "Default")
      (node (ref "U1") (pin "V23") (pinfunction "IO_L21P_1_V23") (pintype "bidirectional"))
    )
    (net (code "459") (name "/SRAM2_D12") (class "Default")
      (node (ref "U1") (pin "V21") (pinfunction "IO_L10P_1_V21") (pintype "bidirectional"))
    )
    (net (code "460") (name "/SRAM2_D13") (class "Default")
      (node (ref "U1") (pin "W23") (pinfunction "IO_L18P_1_W23") (pintype "bidirectional"))
    )
    (net (code "461") (name "/SRAM2_D14") (class "Default")
      (node (ref "U1") (pin "W21") (pinfunction "IO_L04N_1_W21") (pintype "bidirectional"))
    )
    (net (code "462") (name "/SRAM2_D15") (class "Default")
      (node (ref "U1") (pin "Y22") (pinfunction "IO_L13P_1_Y22") (pintype "bidirectional"))
    )
    (net (code "464") (name "/SRAM2_NBHE") (class "Default")
      (node (ref "U1") (pin "AB26") (pinfunction "IO_L06N_1_AB26") (pintype "bidirectional"))
    )
    (net (code "465") (name "/SRAM2_NBLE") (class "Default")
      (node (ref "U1") (pin "AA24") (pinfunction "IO_L11P_1_AA24") (pintype "bidirectional"))
    )
    (net (code "466") (name "/SRAM2_NCS") (class "Default")
      (node (ref "U1") (pin "AB24") (pinfunction "IO_L07N_1/VREF_1_AB24") (pintype "bidirectional"))
    )
    (net (code "467") (name "/SRAM2_NOE") (class "Default")
      (node (ref "U1") (pin "AC26") (pinfunction "IO_L06P_1_AC26") (pintype "bidirectional"))
    )
    (net (code "468") (name "/SRAM2_NWE") (class "Default")
      (node (ref "U1") (pin "T17") (pinfunction "IO_L17N_1_T17") (pintype "bidirectional"))
    )
    (net (code "469") (name "/STATUS_LED") (class "Default")
      (node (ref "NT6") (pin "1") (pinfunction "Net1_1") (pintype "passive"))
    )
    (net (code "470") (name "/SUSPEND") (class "Default")
      (node (ref "R25") (pin "2") (pinfunction "2_2") (pintype "passive"))
    )
    (net (code "471") (name "/SW0") (class "Default")
      (node (ref "U1") (pin "AA9") (pinfunction "IP_2/VREF_2_AA9") (pintype "input"))
    )
    (net (code "472") (name "/SW1") (class "Default")
      (node (ref "U1") (pin "AF17") (pinfunction "IP_2/VREF_2_AF17") (pintype "input"))
    )
    (net (code "473") (name "/SW2") (class "Default")
      (node (ref "U1") (pin "AD9") (pinfunction "IP_2_AD9") (pintype "input"))
    )
    (net (code "474") (name "/SW3") (class "Default")
      (node (ref "U1") (pin "AD10") (pinfunction "IP_2_AD10") (pintype "input"))
    )
    (net (code "475") (name "/SW4") (class "Default")
      (node (ref "U1") (pin "AF22") (pinfunction "IP_2/VREF_2_AF22") (pintype "input"))
    )
    (net (code "477") (name "/TCK") (class "Default")
      (node (ref "R9") (pin "2") (pinfunction "2_2") (pintype "passive"))
    )
    (net (code "478") (name "/TDI") (class "Default")
      (node (ref "R12") (pin "2") (pinfunction "2_2") (pintype "passive"))
    )
    (net (code "479") (name "/TDO") (class "Default")
      (node (ref "R10") (pin "2") (pinfunction "2_2") (pintype "passive"))
    )
    (net (code "481") (name "/TMS") (class "Default")
      (node (ref "R8") (pin "2") (pinfunction "2_2") (pintype "passive"))
    )
    (net (code "500") (name "3V3") (class "Default")
      (node (ref "R1") (pin "2") (pinfunction "2_2") (pintype "passive"))
      (node (ref "R2") (pin "2") (pinfunction "2_2") (pintype "passive"))
      (node (ref "R3") (pin "2") (pinfunction "2_2") (pintype "passive"))
      (node (ref "R4") (pin "2") (pinfunction "2_2") (pintype "passive"))
      (node (ref "U3") (pin "5") (pinfunction "VCC_5") (pintype "power_in"))
    )
    (net (code "501") (name "GND") (class "Default")
      (node (ref "NT2") (pin "2") (pinfunction "Net2_2") (pintype "passive"))
      (node (ref "NT3") (pin "2") (pinfunction "Net2_2") (pintype "passive"))
      (node (ref "NT4") (pin "2") (pinfunction "Net2_2") (pintype "passive"))
      (node (ref "NT5") (pin "2") (pinfunction "Net2_2") (pintype "passive"))
      (node (ref "U3") (pin "3") (pinfunction "GND_3") (pintype "power_in"))
    )
    (net (code "502") (name "Net-(U3-Y)") (class "Default")
      (node (ref "R25") (pin "1") (pinfunction "1_1") (pintype "passive"))
      (node (ref "U3") (pin "4") (pinfunction "Y_4") (pintype "output"))
    )
    (net (code "503") (name "unconnected-(U1B-IO_L27N_1{slash}A7-PadR17)") (class "Default")
      (node (ref "U1") (pin "R17") (pinfunction "IO_L27N_1/A7_R17") (pintype "bidirectional+no_connect"))
    )
    (net (code "504") (name "unconnected-(U1D-IO_L15P_3-PadL10)") (class "Default")
      (node (ref "U1") (pin "L10") (pinfunction "IO_L15P_3_L10") (pintype "bidirectional+no_connect"))
    )
    (net (code "505") (name "unconnected-(U1D-IO_L21P_3-PadM10)") (class "Default")
      (node (ref "U1") (pin "M10") (pinfunction "IO_L21P_3_M10") (pintype "bidirectional+no_connect"))
    )
    (net (code "506") (name "unconnected-(U1D-IO_L35N_3{slash}LHCLK7-PadP10)") (class "Default")
      (node (ref "U1") (pin "P10") (pinfunction "IO_L35N_3/LHCLK7_P10") (pintype "bidirectional+no_connect"))
    )
    (net (code "507") (name "unconnected-(U1E-IP_0-PadA5)") (class "Default")
      (node (ref "U1") (pin "A5") (pinfunction "IP_0_A5") (pintype "input+no_connect"))
    )
    (net (code "508") (name "unconnected-(U1E-IP_0-PadA7)") (class "Default")
      (node (ref "U1") (pin "A7") (pinfunction "IP_0_A7") (pintype "input+no_connect"))
    )
    (net (code "509") (name "unconnected-(U1E-IP_0-PadA13)") (class "Default")
      (node (ref "U1") (pin "A13") (pinfunction "IP_0_A13") (pintype "input+no_connect"))
    )
    (net (code "510") (name "unconnected-(U1E-IP_0-PadA17)") (class "Default")
      (node (ref "U1") (pin "A17") (pinfunction "IP_0_A17") (pintype "input+no_connect"))
    )
    (net (code "511") (name "unconnected-(U1E-IP_0-PadA23)") (class "Default")
      (node (ref "U1") (pin "A23") (pinfunction "IP_0_A23") (pintype "input+no_connect"))
    )
    (net (code "512") (name "unconnected-(U1E-IP_0-PadA24)") (class "Default")
      (node (ref "U1") (pin "A24") (pinfunction "IP_0_A24") (pintype "input+no_connect"))
    )
    (net (code "513") (name "unconnected-(U1E-IP_0-PadB24)") (class "Default")
      (node (ref "U1") (pin "B24") (pinfunction "IP_0_B24") (pintype "input+no_connect"))
    )
    (net (code "514") (name "unconnected-(U1E-IP_0-PadC4)") (class "Default")
      (node (ref "U1") (pin "C4") (pinfunction "IP_0_C4") (pintype "input+no_connect"))
    )
    (net (code "515") (name "unconnected-(U1E-IP_0-PadD5)") (class "Default")
      (node (ref "U1") (pin "D5") (pinfunction "IP_0_D5") (pintype "input+no_connect"))
    )
    (net (code "516") (name "unconnected-(U1E-IP_0-PadD12)") (class "Default")
      (node (ref "U1") (pin "D12") (pinfunction "IP_0_D12") (pintype "input+no_connect"))
    )
    (net (code "517") (name "unconnected-(U1E-IP_0-PadD15)") (class "Default")
      (node (ref "U1") (pin "D15") (pinfunction "IP_0_D15") (pintype "input+no_connect"))
    )
    (net (code "518") (name "unconnected-(U1E-IP_0-PadD19)") (class "Default")
      (node (ref "U1") (pin "D19") (pinfunction "IP_0_D19") (pintype "input+no_connect"))
    )
    (net (code "519") (name "unconnected-(U1E-IP_0-PadE6)") (class "Default")
      (node (ref "U1") (pin "E6") (pinfunction "IP_0_E6") (pintype "input"))
    )
    (net (code "520") (name "unconnected-(U1E-IP_0-PadE9)") (class "Default")
      (node (ref "U1") (pin "E9") (pinfunction "IP_0_E9") (pintype "input"))
    )
    (net (code "521") (name "unconnected-(U1E-IP_0-PadE11)") (class "Default")
      (node (ref "U1") (pin "E11") (pinfunction "IP_0_E11") (pintype "input"))
    )
    (net (code "522") (name "unconnected-(U1E-IP_0-PadE18)") (class "Default")
      (node (ref "U1") (pin "E18") (pinfunction "IP_0_E18") (pintype "input"))
    )
    (net (code "523") (name "unconnected-(U1E-IP_0-PadE20)") (class "Default")
      (node (ref "U1") (pin "E20") (pinfunction "IP_0_E20") (pintype "input"))
    )
    (net (code "524") (name "unconnected-(U1E-IP_0-PadF9)") (class "Default")
      (node (ref "U1") (pin "F9") (pinfunction "IP_0_F9") (pintype "input"))
    )
    (net (code "525") (name "unconnected-(U1E-IP_0-PadF10)") (class "Default")
      (node (ref "U1") (pin "F10") (pinfunction "IP_0_F10") (pintype "input"))
    )
    (net (code "526") (name "unconnected-(U1E-IP_0-PadF18)") (class "Default")
      (node (ref "U1") (pin "F18") (pinfunction "IP_0_F18") (pintype "input"))
    )
    (net (code "527") (name "unconnected-(U1E-IP_0-PadG14)") (class "Default")
      (node (ref "U1") (pin "G14") (pinfunction "IP_0_G14") (pintype "input"))
    )
    (net (code "528") (name "unconnected-(U1E-IP_0-PadG16)") (class "Default")
      (node (ref "U1") (pin "G16") (pinfunction "IP_0_G16") (pintype "input"))
    )
    (net (code "529") (name "unconnected-(U1E-IP_0-PadG18)") (class "Default")
      (node (ref "U1") (pin "G18") (pinfunction "IP_0_G18") (pintype "input"))
    )
    (net (code "530") (name "unconnected-(U1E-IP_0-PadH13)") (class "Default")
      (node (ref "U1") (pin "H13") (pinfunction "IP_0_H13") (pintype "input"))
    )
    (net (code "531") (name "unconnected-(U1E-IP_0-PadH18)") (class "Default")
      (node (ref "U1") (pin "H18") (pinfunction "IP_0_H18") (pintype "input"))
    )
    (net (code "532") (name "unconnected-(U1E-IP_0-PadJ10)") (class "Default")
      (node (ref "U1") (pin "J10") (pinfunction "IP_0_J10") (pintype "input"))
    )
    (net (code "533") (name "unconnected-(U1E-IP_0-PadJ13)") (class "Default")
      (node (ref "U1") (pin "J13") (pinfunction "IP_0_J13") (pintype "input"))
    )
    (net (code "534") (name "unconnected-(U1E-IP_0-PadJ15)") (class "Default")
      (node (ref "U1") (pin "J15") (pinfunction "IP_0_J15") (pintype "input"))
    )
    (net (code "535") (name "unconnected-(U1E-IP_0{slash}VREF_0-PadD7)") (class "Default")
      (node (ref "U1") (pin "D7") (pinfunction "IP_0/VREF_0_D7") (pintype "input+no_connect"))
    )
    (net (code "536") (name "unconnected-(U1E-IP_0{slash}VREF_0-PadD14)") (class "Default")
      (node (ref "U1") (pin "D14") (pinfunction "IP_0/VREF_0_D14") (pintype "input+no_connect"))
    )
    (net (code "537") (name "unconnected-(U1E-IP_0{slash}VREF_0-PadG11)") (class "Default")
      (node (ref "U1") (pin "G11") (pinfunction "IP_0/VREF_0_G11") (pintype "input"))
    )
    (net (code "538") (name "unconnected-(U1E-IP_0{slash}VREF_0-PadJ17)") (class "Default")
      (node (ref "U1") (pin "J17") (pinfunction "IP_0/VREF_0_J17") (pintype "input"))
    )
    (net (code "539") (name "unconnected-(U1E-IP_2-PadAA8)") (class "Default")
      (node (ref "U1") (pin "AA8") (pinfunction "IP_2_AA8") (pintype "input"))
    )
    (net (code "540") (name "unconnected-(U1E-IP_2-PadAA19)") (class "Default")
      (node (ref "U1") (pin "AA19") (pinfunction "IP_2_AA19") (pintype "input"))
    )
    (net (code "541") (name "unconnected-(U1E-IP_2-PadAB17)") (class "Default")
      (node (ref "U1") (pin "AB17") (pinfunction "IP_2_AB17") (pintype "input"))
    )
    (net (code "542") (name "unconnected-(U1E-IP_2-PadAB20)") (class "Default")
      (node (ref "U1") (pin "AB20") (pinfunction "IP_2_AB20") (pintype "input"))
    )
    (net (code "543") (name "unconnected-(U1E-IP_2-PadAC5)") (class "Default")
      (node (ref "U1") (pin "AC5") (pinfunction "IP_2_AC5") (pintype "input"))
    )
    (net (code "544") (name "unconnected-(U1E-IP_2-PadAC7)") (class "Default")
      (node (ref "U1") (pin "AC7") (pinfunction "IP_2_AC7") (pintype "input"))
    )
    (net (code "545") (name "unconnected-(U1E-IP_2-PadAC17)") (class "Default")
      (node (ref "U1") (pin "AC17") (pinfunction "IP_2_AC17") (pintype "input"))
    )
    (net (code "546") (name "unconnected-(U1E-IP_2-PadAC18)") (class "Default")
      (node (ref "U1") (pin "AC18") (pinfunction "IP_2_AC18") (pintype "input"))
    )
    (net (code "547") (name "unconnected-(U1E-IP_2-PadAD5)") (class "Default")
      (node (ref "U1") (pin "AD5") (pinfunction "IP_2_AD5") (pintype "input"))
    )
    (net (code "548") (name "unconnected-(U1E-IP_2-PadAD16)") (class "Default")
      (node (ref "U1") (pin "AD16") (pinfunction "IP_2_AD16") (pintype "input"))
    )
    (net (code "549") (name "unconnected-(U1E-IP_2-PadAD23)") (class "Default")
      (node (ref "U1") (pin "AD23") (pinfunction "IP_2_AD23") (pintype "input"))
    )
    (net (code "550") (name "unconnected-(U1E-IP_2-PadAF2)") (class "Default")
      (node (ref "U1") (pin "AF2") (pinfunction "IP_2_AF2") (pintype "input"))
    )
    (net (code "551") (name "unconnected-(U1E-IP_2-PadAF7)") (class "Default")
      (node (ref "U1") (pin "AF7") (pinfunction "IP_2_AF7") (pintype "input"))
    )
    (net (code "552") (name "unconnected-(U1E-IP_2-PadW18)") (class "Default")
      (node (ref "U1") (pin "W18") (pinfunction "IP_2_W18") (pintype "input"))
    )
    (net (code "553") (name "unconnected-(U1E-IP_2-PadY8)") (class "Default")
      (node (ref "U1") (pin "Y8") (pinfunction "IP_2_Y8") (pintype "input"))
    )
    (net (code "554") (name "unconnected-(U1E-IP_2-PadY11)") (class "Default")
      (node (ref "U1") (pin "Y11") (pinfunction "IP_2_Y11") (pintype "input"))
    )
    (net (code "555") (name "unconnected-(U1E-IP_2-PadY18)") (class "Default")
      (node (ref "U1") (pin "Y18") (pinfunction "IP_2_Y18") (pintype "input"))
    )
    (net (code "556") (name "unconnected-(U1E-IP_2{slash}VREF_2-PadAA20)") (class "Default")
      (node (ref "U1") (pin "AA20") (pinfunction "IP_2/VREF_2_AA20") (pintype "input"))
    )
    (net (code "557") (name "unconnected-(U1E-IP_2{slash}VREF_2-PadAB10)") (class "Default")
      (node (ref "U1") (pin "AB10") (pinfunction "IP_2/VREF_2_AB10") (pintype "input"))
    )
    (net (code "558") (name "unconnected-(U1E-IP_2{slash}VREF_2-PadY16)") (class "Default")
      (node (ref "U1") (pin "Y16") (pinfunction "IP_2/VREF_2_Y16") (pintype "input"))
    )
    (net (code "559") (name "unconnected-(U1E-IP_2{slash}VREF_2-PadY19)") (class "Default")
      (node (ref "U1") (pin "Y19") (pinfunction "IP_2/VREF_2_Y19") (pintype "input"))
    )
    (net (code "560") (name "unconnected-(U1E-IP_L04N_3{slash}VREF_3-PadC1)") (class "Default")
      (node (ref "U1") (pin "C1") (pinfunction "IP_L04N_3/VREF_3_C1") (pintype "input"))
    )
    (net (code "561") (name "unconnected-(U1E-IP_L04P_3-PadC2)") (class "Default")
      (node (ref "U1") (pin "C2") (pinfunction "IP_L04P_3_C2") (pintype "input"))
    )
    (net (code "562") (name "unconnected-(U1E-IP_L08N_3-PadD1)") (class "Default")
      (node (ref "U1") (pin "D1") (pinfunction "IP_L08N_3_D1") (pintype "input"))
    )
    (net (code "563") (name "unconnected-(U1E-IP_L08P_3-PadD2)") (class "Default")
      (node (ref "U1") (pin "D2") (pinfunction "IP_L08P_3_D2") (pintype "input"))
    )
    (net (code "564") (name "unconnected-(U1E-IP_L12N_3{slash}VREF_3-PadH4)") (class "Default")
      (node (ref "U1") (pin "H4") (pinfunction "IP_L12N_3/VREF_3_H4") (pintype "input"))
    )
    (net (code "565") (name "unconnected-(U1E-IP_L12P_3-PadG5)") (class "Default")
      (node (ref "U1") (pin "G5") (pinfunction "IP_L12P_3_G5") (pintype "input"))
    )
    (net (code "566") (name "unconnected-(U1E-IP_L16N_1-PadY26)") (class "Default")
      (node (ref "U1") (pin "Y26") (pinfunction "IP_L16N_1_Y26") (pintype "input"))
    )
    (net (code "567") (name "unconnected-(U1E-IP_L16N_3-PadG1)") (class "Default")
      (node (ref "U1") (pin "G1") (pinfunction "IP_L16N_3_G1") (pintype "input"))
    )
    (net (code "568") (name "unconnected-(U1E-IP_L16P_1-PadW25)") (class "Default")
      (node (ref "U1") (pin "W25") (pinfunction "IP_L16P_1_W25") (pintype "input"))
    )
    (net (code "569") (name "unconnected-(U1E-IP_L16P_3-PadG2)") (class "Default")
      (node (ref "U1") (pin "G2") (pinfunction "IP_L16P_3_G2") (pintype "input"))
    )
    (net (code "570") (name "unconnected-(U1E-IP_L20N_1{slash}VREF_1-PadV26)") (class "Default")
      (node (ref "U1") (pin "V26") (pinfunction "IP_L20N_1/VREF_1_V26") (pintype "input"))
    )
    (net (code "571") (name "unconnected-(U1E-IP_L20N_3{slash}VREF_3-PadJ2)") (class "Default")
      (node (ref "U1") (pin "J2") (pinfunction "IP_L20N_3/VREF_3_J2") (pintype "input"))
    )
    (net (code "572") (name "unconnected-(U1E-IP_L20P_1-PadW26)") (class "Default")
      (node (ref "U1") (pin "W26") (pinfunction "IP_L20P_1_W26") (pintype "input"))
    )
    (net (code "573") (name "unconnected-(U1E-IP_L20P_3-PadJ3)") (class "Default")
      (node (ref "U1") (pin "J3") (pinfunction "IP_L20P_3_J3") (pintype "input"))
    )
    (net (code "574") (name "unconnected-(U1E-IP_L24N_1{slash}VREF_1-PadU26)") (class "Default")
      (node (ref "U1") (pin "U26") (pinfunction "IP_L24N_1/VREF_1_U26") (pintype "input"))
    )
    (net (code "575") (name "unconnected-(U1E-IP_L24N_3-PadK1)") (class "Default")
      (node (ref "U1") (pin "K1") (pinfunction "IP_L24N_3_K1") (pintype "input"))
    )
    (net (code "576") (name "unconnected-(U1E-IP_L24P_1-PadU25)") (class "Default")
      (node (ref "U1") (pin "U25") (pinfunction "IP_L24P_1_U25") (pintype "input"))
    )
    (net (code "577") (name "unconnected-(U1E-IP_L24P_3-PadJ1)") (class "Default")
      (node (ref "U1") (pin "J1") (pinfunction "IP_L24P_3_J1") (pintype "input"))
    )
    (net (code "578") (name "unconnected-(U1E-IP_L28N_1-PadR24)") (class "Default")
      (node (ref "U1") (pin "R24") (pinfunction "IP_L28N_1_R24") (pintype "input"))
    )
    (net (code "579") (name "unconnected-(U1E-IP_L28P_1{slash}VREF_1-PadR23)") (class "Default")
      (node (ref "U1") (pin "R23") (pinfunction "IP_L28P_1/VREF_1_R23") (pintype "input"))
    )
    (net (code "580") (name "unconnected-(U1E-IP_L32N_1-PadN25)") (class "Default")
      (node (ref "U1") (pin "N25") (pinfunction "IP_L32N_1_N25") (pintype "input"))
    )
    (net (code "581") (name "unconnected-(U1E-IP_L32P_1-PadN26)") (class "Default")
      (node (ref "U1") (pin "N26") (pinfunction "IP_L32P_1_N26") (pintype "input"))
    )
    (net (code "582") (name "unconnected-(U1E-IP_L36N_1-PadN23)") (class "Default")
      (node (ref "U1") (pin "N23") (pinfunction "IP_L36N_1_N23") (pintype "input"))
    )
    (net (code "583") (name "unconnected-(U1E-IP_L36P_1{slash}VREF_1-PadM24)") (class "Default")
      (node (ref "U1") (pin "M24") (pinfunction "IP_L36P_1/VREF_1_M24") (pintype "input"))
    )
    (net (code "584") (name "unconnected-(U1E-IP_L40N_1-PadL23)") (class "Default")
      (node (ref "U1") (pin "L23") (pinfunction "IP_L40N_1_L23") (pintype "input"))
    )
    (net (code "585") (name "unconnected-(U1E-IP_L40P_1-PadK24)") (class "Default")
      (node (ref "U1") (pin "K24") (pinfunction "IP_L40P_1_K24") (pintype "input"))
    )
    (net (code "586") (name "unconnected-(U1E-IP_L44N_1-PadH25)") (class "Default")
      (node (ref "U1") (pin "H25") (pinfunction "IP_L44N_1_H25") (pintype "input"))
    )
    (net (code "587") (name "unconnected-(U1E-IP_L44P_1{slash}VREF_1-PadH26)") (class "Default")
      (node (ref "U1") (pin "H26") (pinfunction "IP_L44P_1/VREF_1_H26") (pintype "input"))
    )
    (net (code "588") (name "unconnected-(U1E-IP_L46N_3-PadV4)") (class "Default")
      (node (ref "U1") (pin "V4") (pinfunction "IP_L46N_3_V4") (pintype "input"))
    )
    (net (code "589") (name "unconnected-(U1E-IP_L46P_3-PadU3)") (class "Default")
      (node (ref "U1") (pin "U3") (pinfunction "IP_L46P_3_U3") (pintype "input"))
    )
    (net (code "590") (name "unconnected-(U1E-IP_L48N_1-PadH24)") (class "Default")
      (node (ref "U1") (pin "H24") (pinfunction "IP_L48N_1_H24") (pintype "input"))
    )
    (net (code "591") (name "unconnected-(U1E-IP_L48P_1-PadH23)") (class "Default")
      (node (ref "U1") (pin "H23") (pinfunction "IP_L48P_1_H23") (pintype "input"))
    )
    (net (code "592") (name "unconnected-(U1E-IP_L50N_3{slash}VREF_3-PadW2)") (class "Default")
      (node (ref "U1") (pin "W2") (pinfunction "IP_L50N_3/VREF_3_W2") (pintype "input"))
    )
    (net (code "593") (name "unconnected-(U1E-IP_L50P_3-PadW1)") (class "Default")
      (node (ref "U1") (pin "W1") (pinfunction "IP_L50P_3_W1") (pintype "input"))
    )
    (net (code "594") (name "unconnected-(U1E-IP_L52N_1{slash}VREF_1-PadG25)") (class "Default")
      (node (ref "U1") (pin "G25") (pinfunction "IP_L52N_1/VREF_1_G25") (pintype "input"))
    )
    (net (code "595") (name "unconnected-(U1E-IP_L52P_1-PadG26)") (class "Default")
      (node (ref "U1") (pin "G26") (pinfunction "IP_L52P_1_G26") (pintype "input"))
    )
    (net (code "596") (name "unconnected-(U1E-IP_L54N_3-PadY4)") (class "Default")
      (node (ref "U1") (pin "Y4") (pinfunction "IP_L54N_3_Y4") (pintype "input"))
    )
    (net (code "597") (name "unconnected-(U1E-IP_L54P_3-PadY3)") (class "Default")
      (node (ref "U1") (pin "Y3") (pinfunction "IP_L54P_3_Y3") (pintype "input"))
    )
    (net (code "598") (name "unconnected-(U1E-IP_L58P_3-PadAA4)") (class "Default")
      (node (ref "U1") (pin "AA4") (pinfunction "IP_L58P_3_AA4") (pintype "input"))
    )
    (net (code "599") (name "unconnected-(U1E-IP_L62N_3-PadAB4)") (class "Default")
      (node (ref "U1") (pin "AB4") (pinfunction "IP_L62N_3_AB4") (pintype "input"))
    )
    (net (code "600") (name "unconnected-(U1E-IP_L62P_3-PadAB3)") (class "Default")
      (node (ref "U1") (pin "AB3") (pinfunction "IP_L62P_3_AB3") (pintype "input"))
    )
    (net (code "601") (name "unconnected-(U1E-IP_L65N_1-PadB25)") (class "Default")
      (node (ref "U1") (pin "B25") (pinfunction "IP_L65N_1_B25") (pintype "input"))
    )
    (net (code "602") (name "unconnected-(U1E-IP_L65P_1{slash}VREF_1-PadB26)") (class "Default")
      (node (ref "U1") (pin "B26") (pinfunction "IP_L65P_1/VREF_1_B26") (pintype "input"))
    )
    (net (code "603") (name "unconnected-(U3-NC-Pad1)") (class "Default")
      (node (ref "U3") (pin "1") (pinfunction "NC_1") (pintype "passive+no_connect"))
    )
  )
)
